# XMICRO_BP8.net
KiCad netlist of a schematic drawn in EAGLE
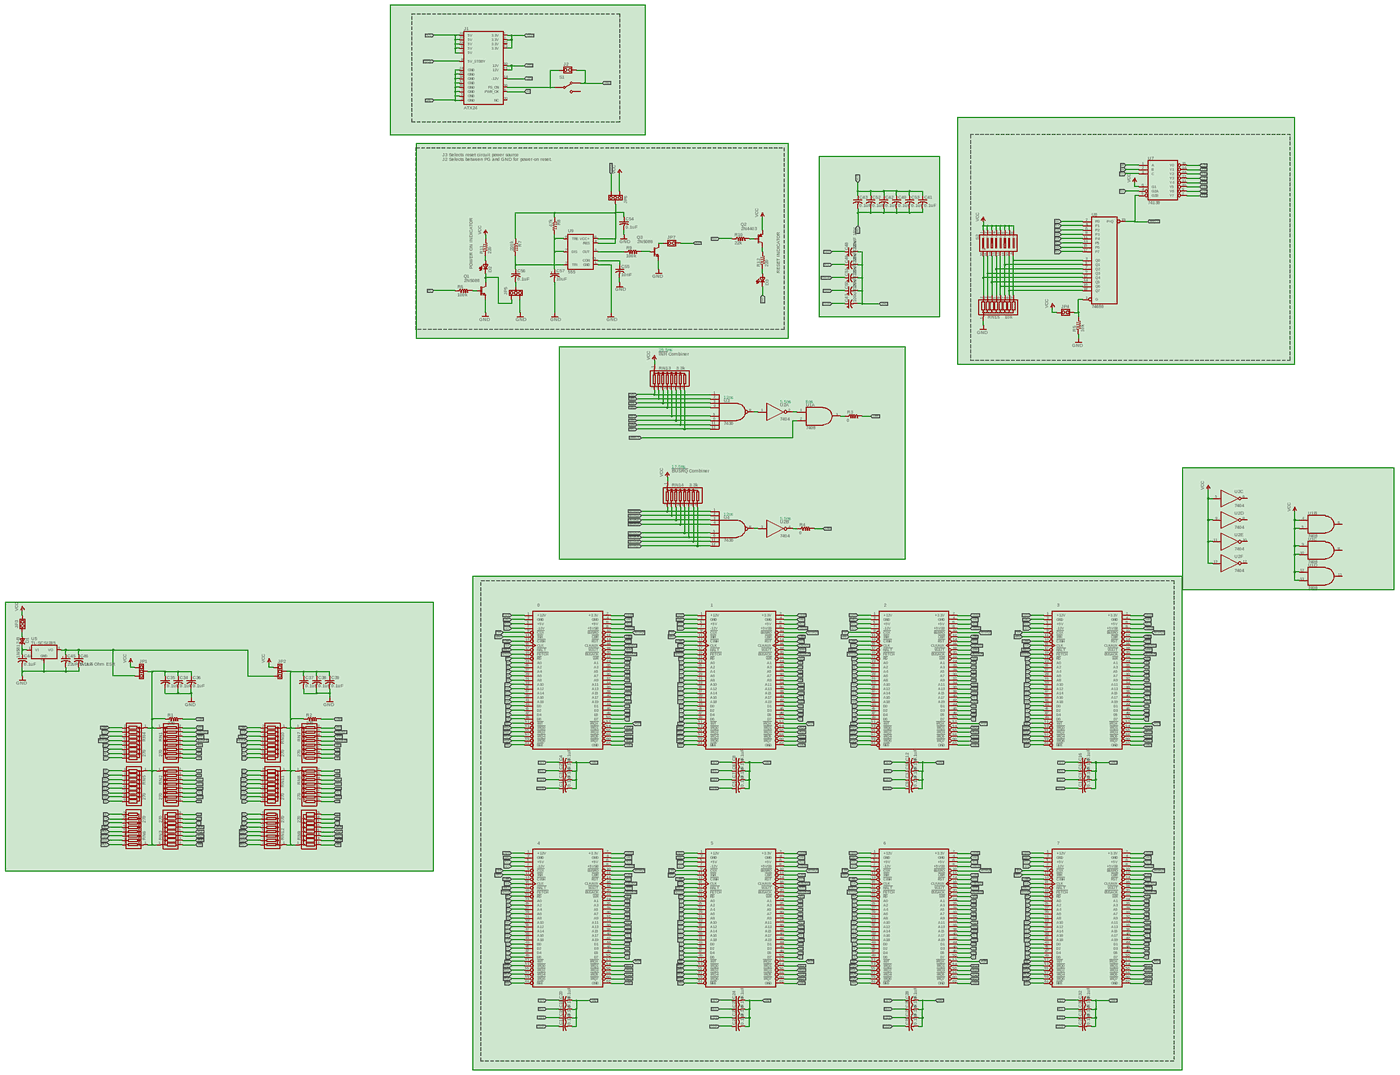
[diagram p0: schematic, sheet 1, overview]
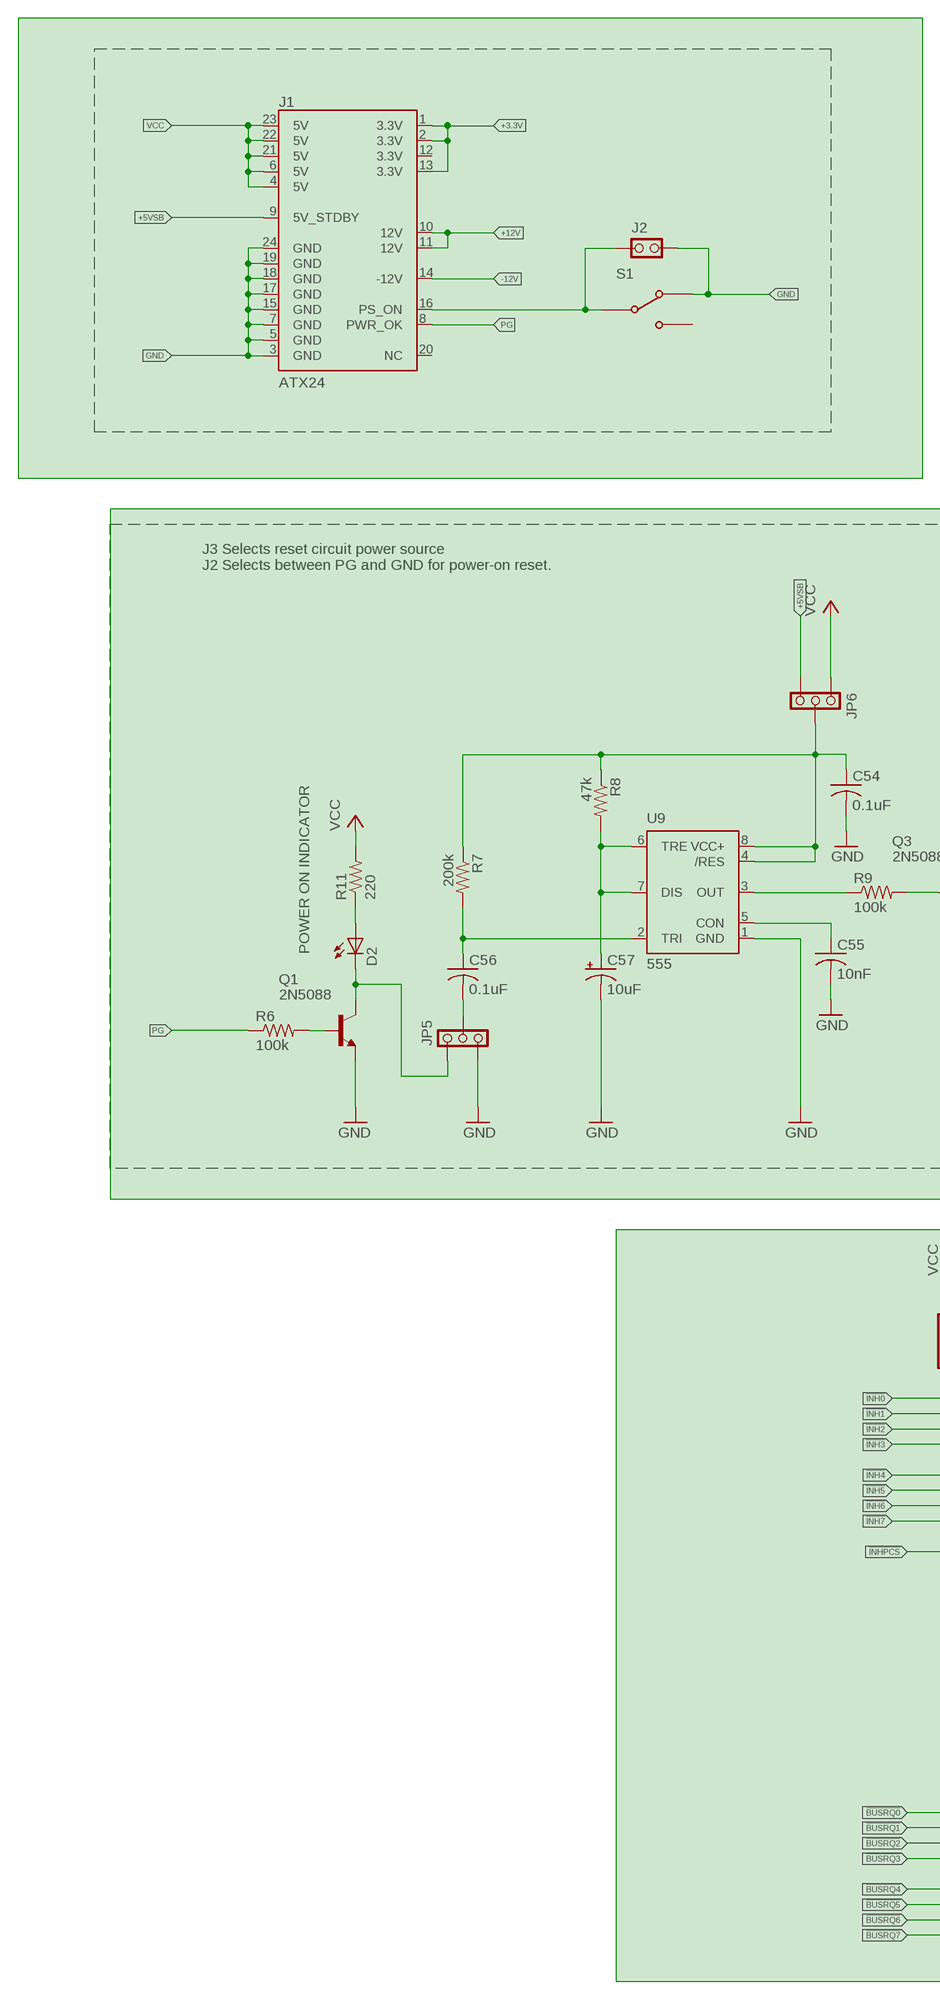
[diagram p1: schematic, sheet 1, part 1 of 4]
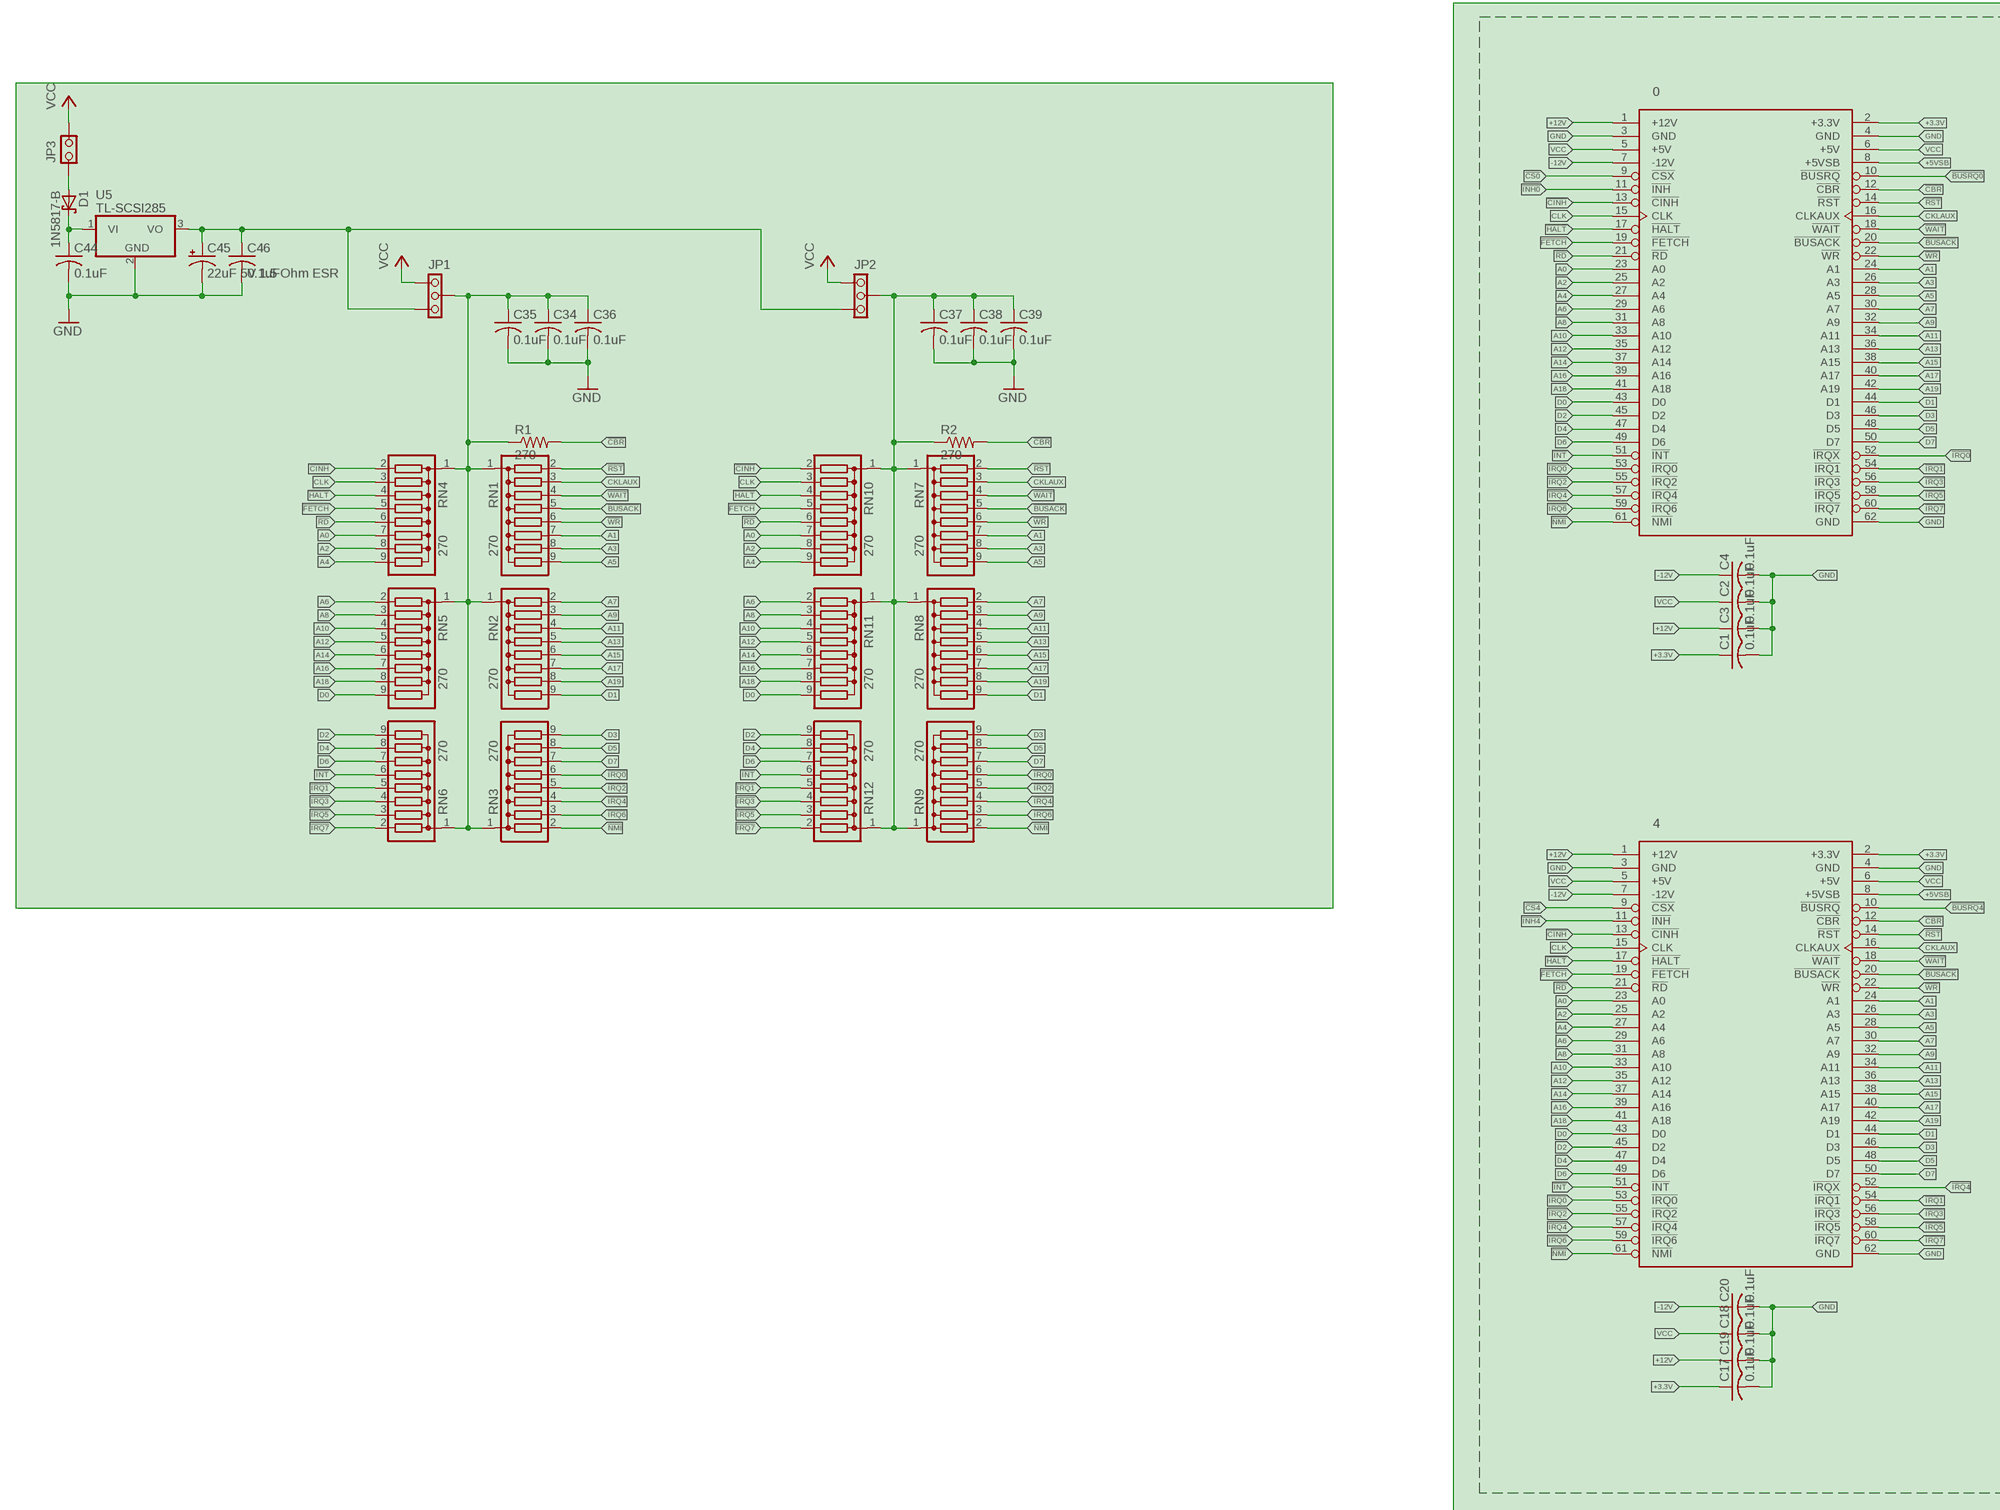
[diagram p2: schematic, sheet 1, part 2 of 4]
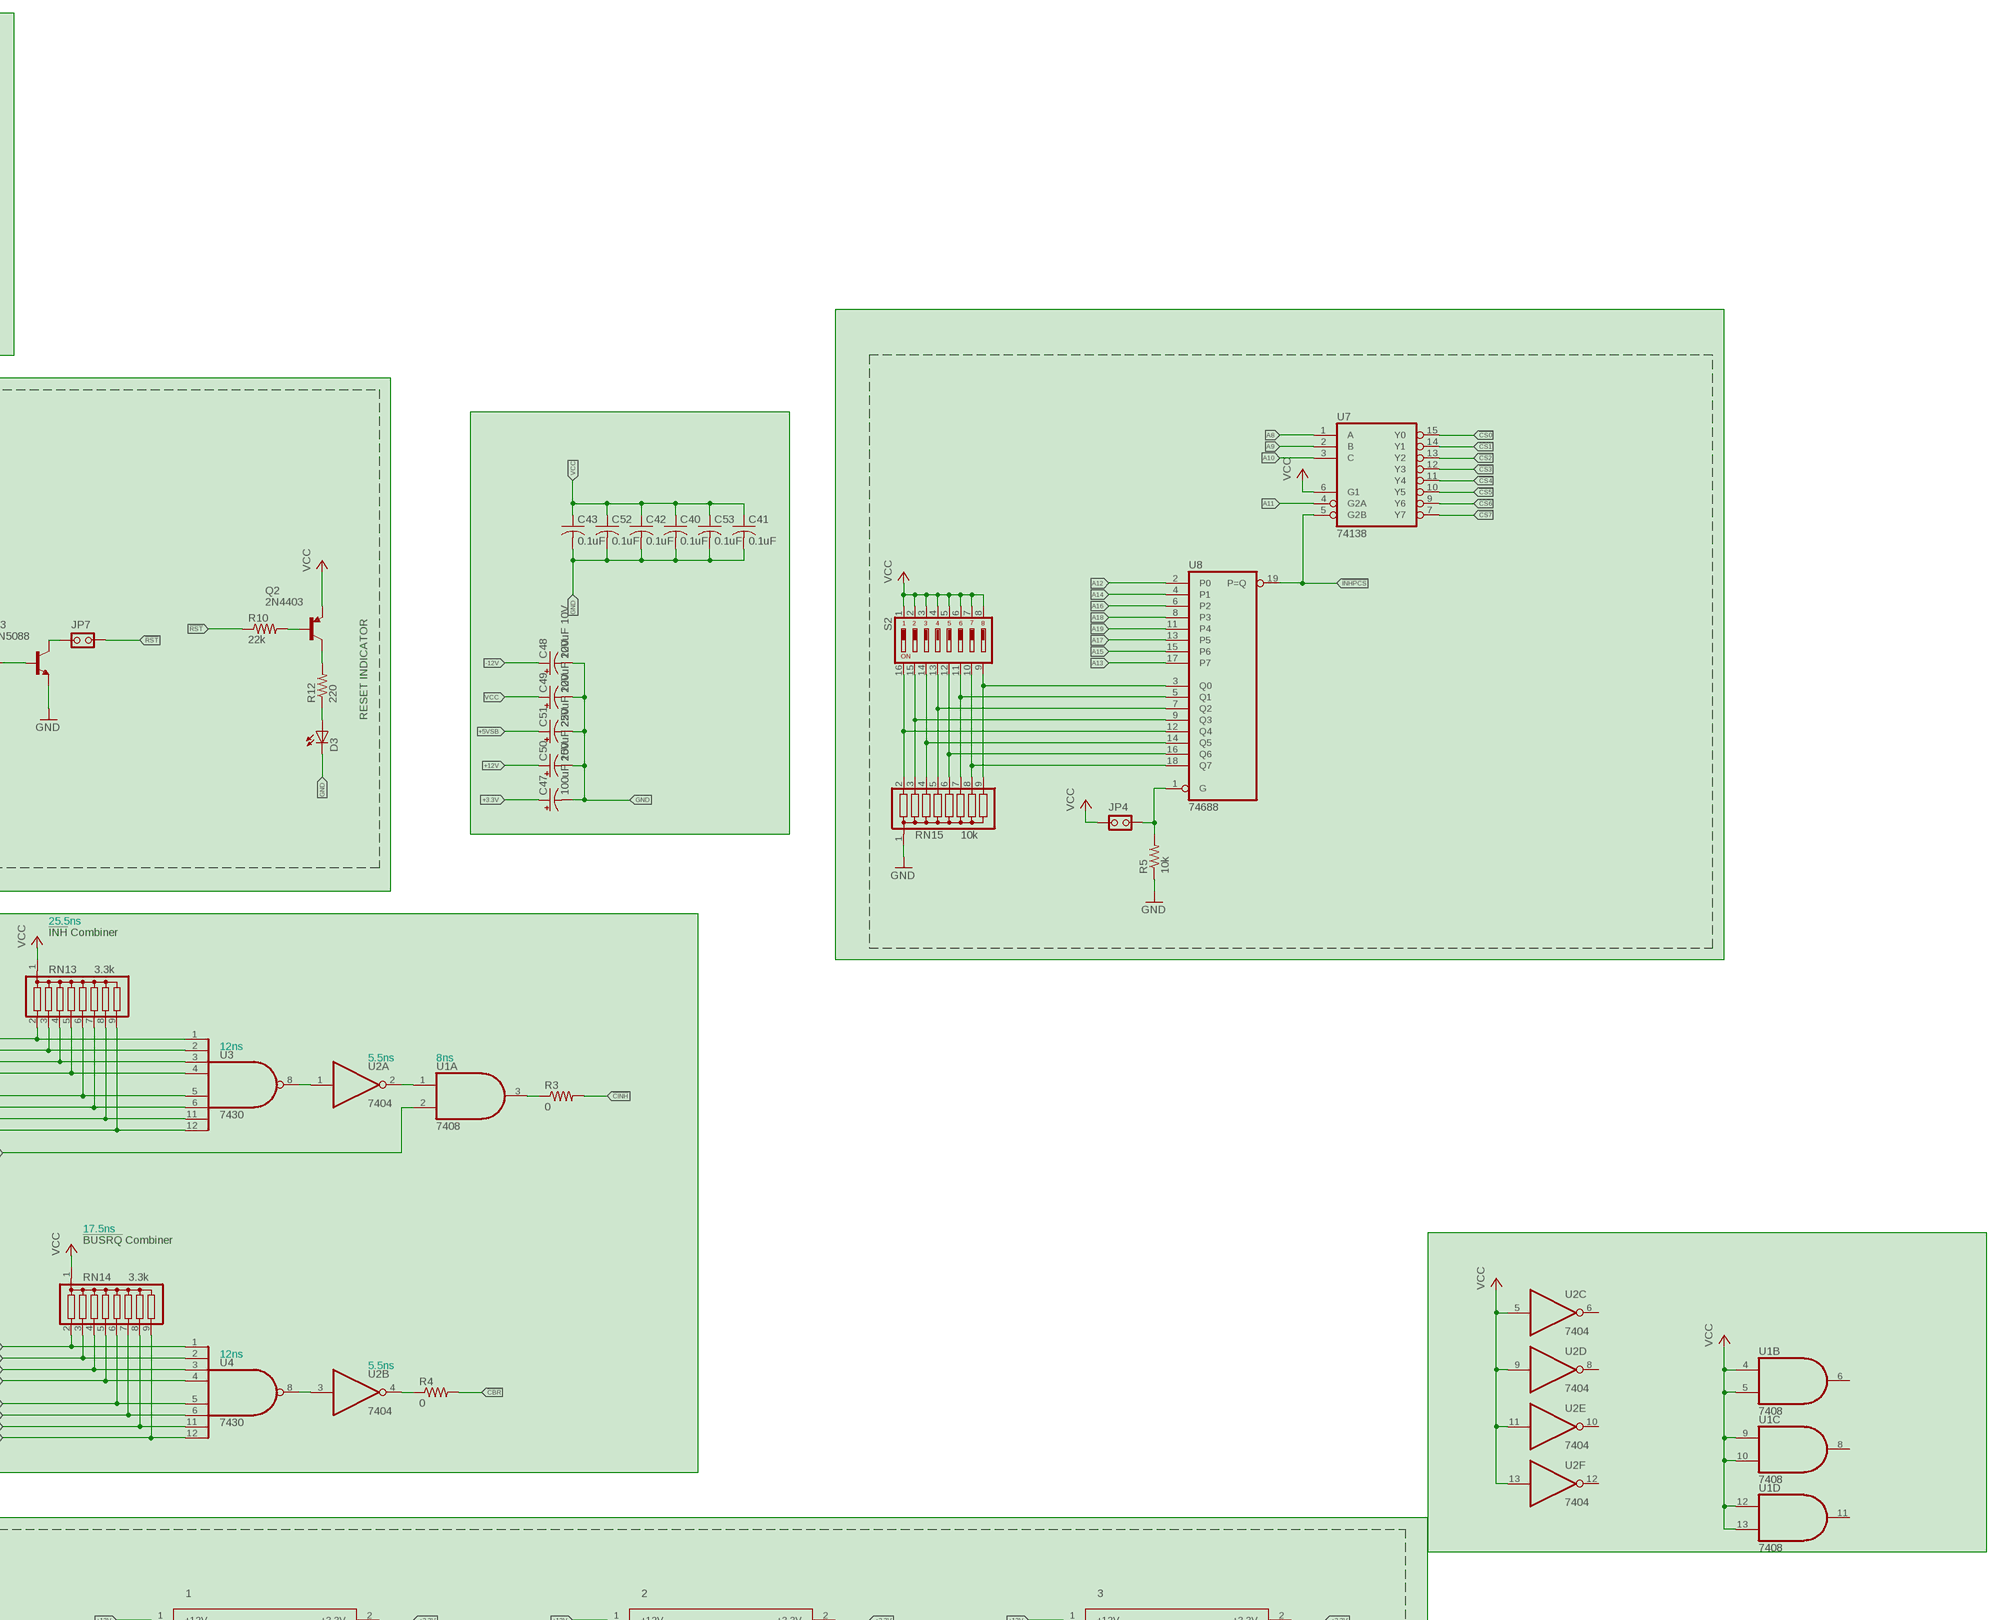
[diagram p3: schematic, sheet 1, part 3 of 4]
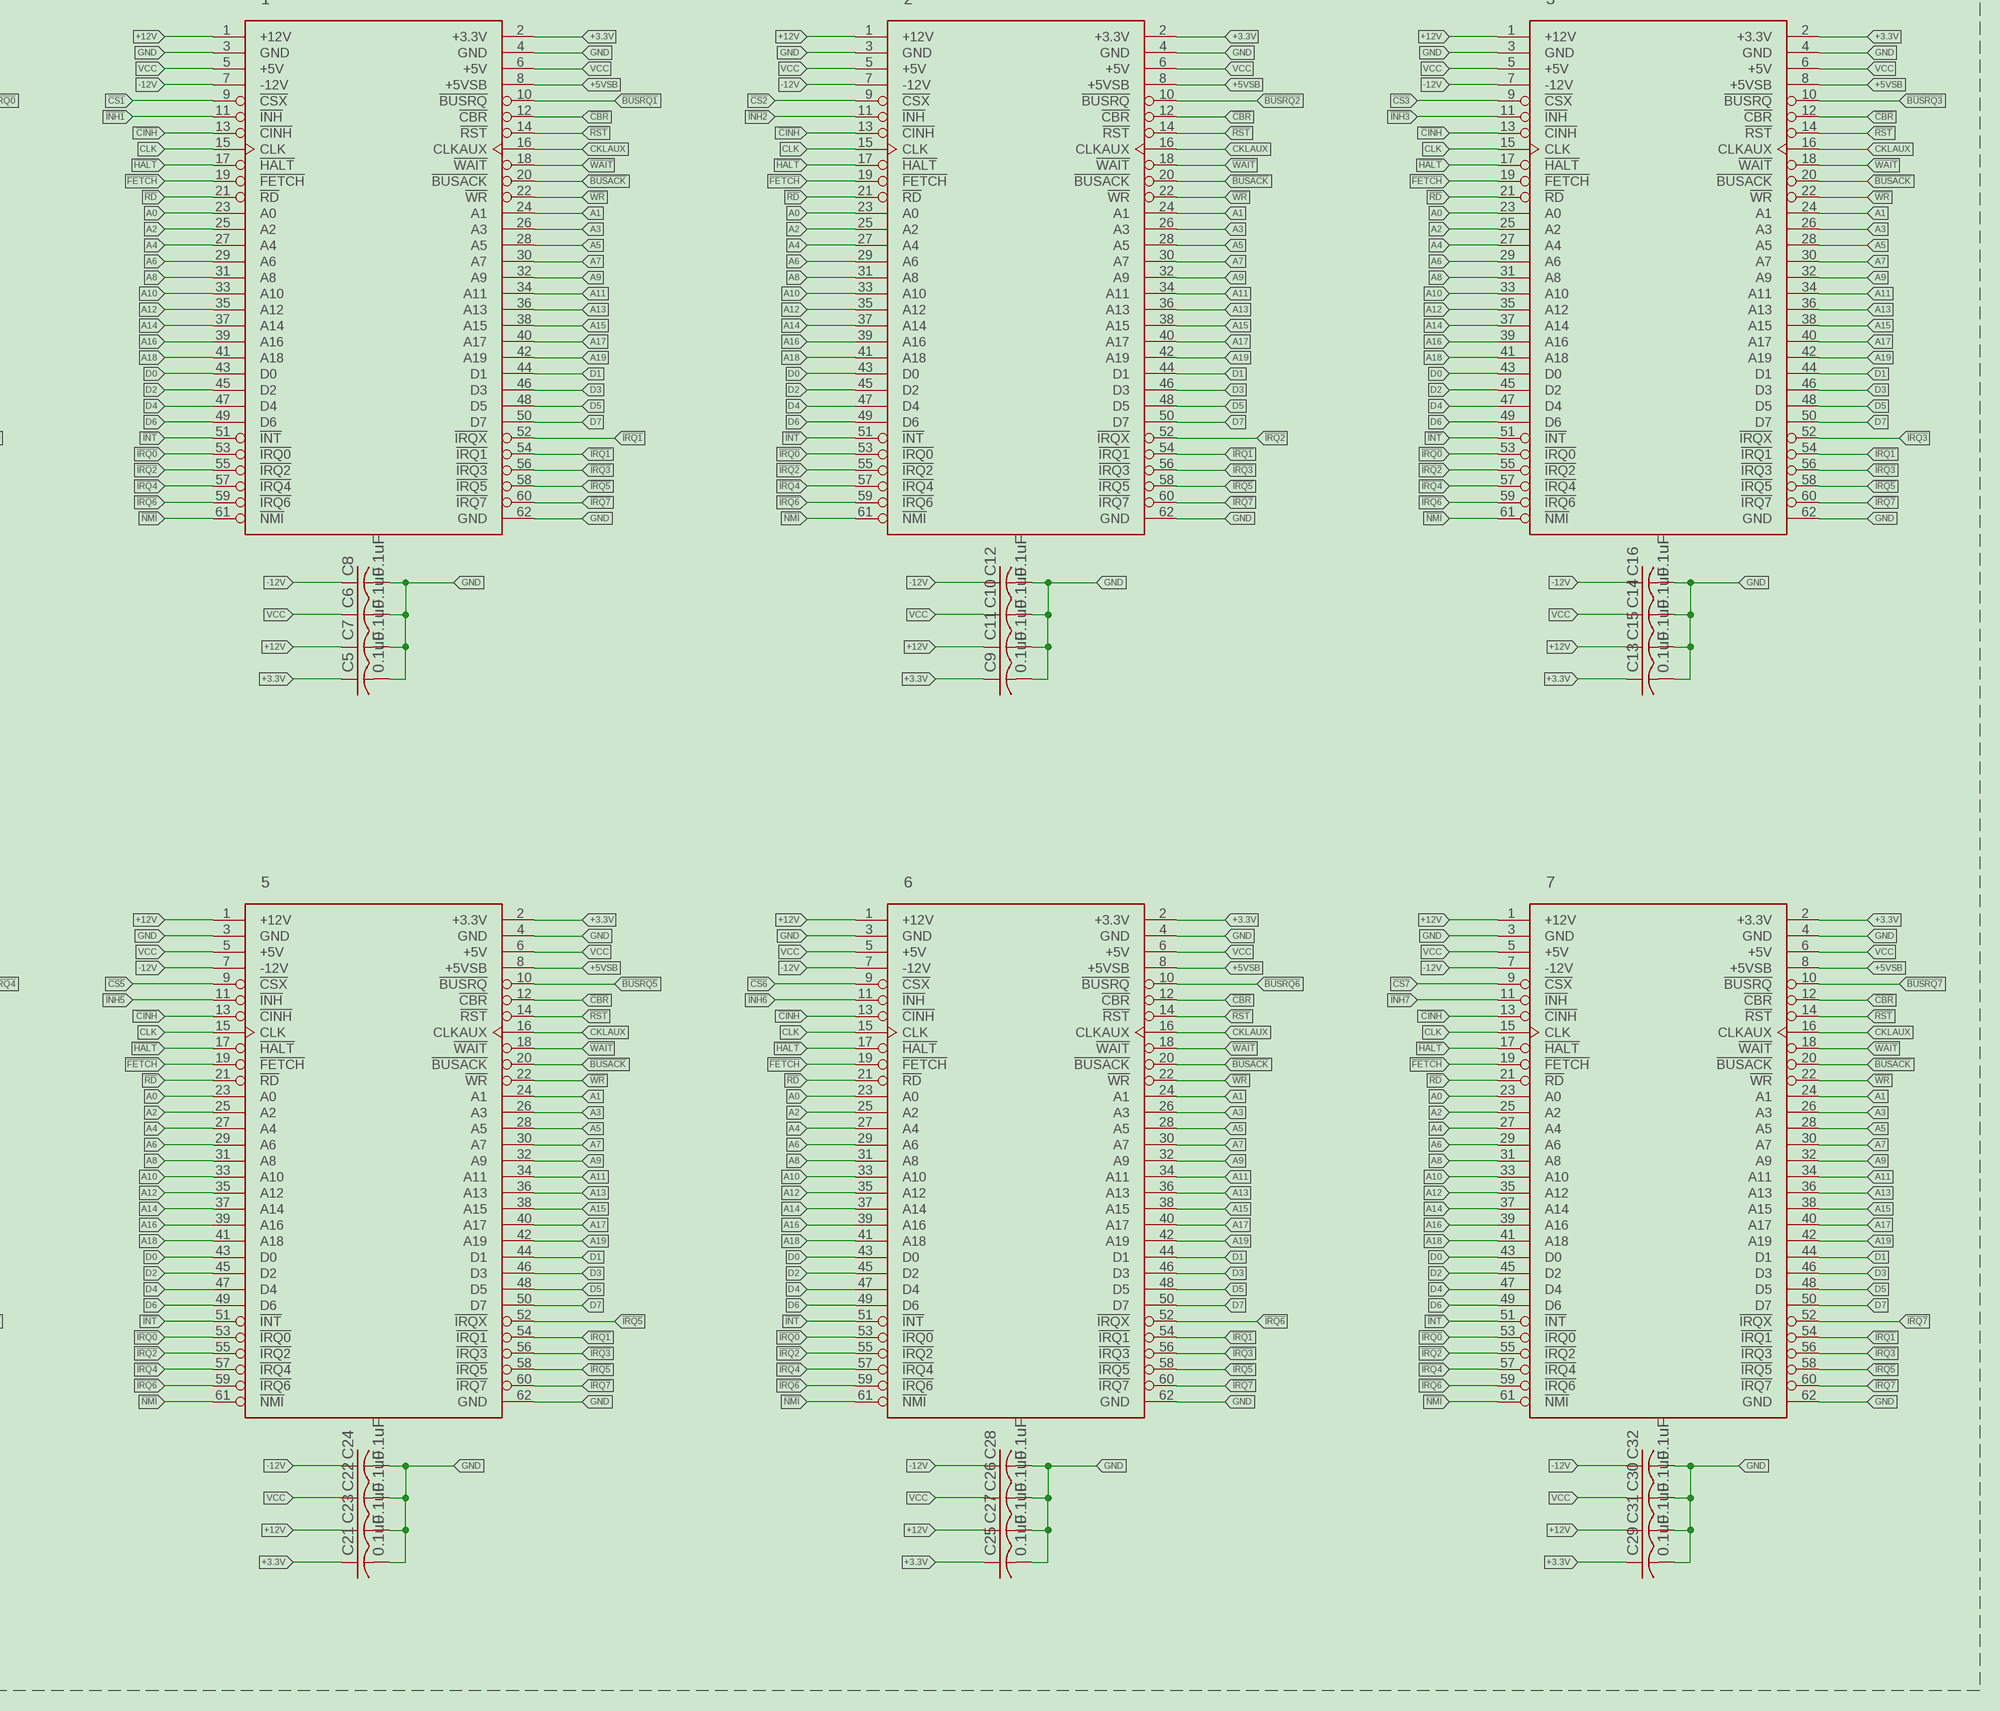
[diagram p4: schematic, sheet 1, part 4 of 4]

(export (version "E")
  (design (tool "Eeschema 10.0.6"))
  (components
    (comp (ref "0")
      (value "XMICRO-BUS-PHYSICAL-EDGE62F")
      (footprint "eagle-import:EDGE62F")
      (libsource (lib "eagle-import") (part "XMICRO-BUS-PHYSICAL-EDGE62F"))
    )
    (comp (ref "1")
      (value "XMICRO-BUS-PHYSICAL-EDGE62F")
      (footprint "eagle-import:EDGE62F")
      (libsource (lib "eagle-import") (part "XMICRO-BUS-PHYSICAL-EDGE62F"))
    )
    (comp (ref "2")
      (value "XMICRO-BUS-PHYSICAL-EDGE62F")
      (footprint "eagle-import:EDGE62F")
      (libsource (lib "eagle-import") (part "XMICRO-BUS-PHYSICAL-EDGE62F"))
    )
    (comp (ref "3")
      (value "XMICRO-BUS-PHYSICAL-EDGE62F")
      (footprint "eagle-import:EDGE62F")
      (libsource (lib "eagle-import") (part "XMICRO-BUS-PHYSICAL-EDGE62F"))
    )
    (comp (ref "4")
      (value "XMICRO-BUS-PHYSICAL-EDGE62F")
      (footprint "eagle-import:EDGE62F")
      (libsource (lib "eagle-import") (part "XMICRO-BUS-PHYSICAL-EDGE62F"))
    )
    (comp (ref "5")
      (value "XMICRO-BUS-PHYSICAL-EDGE62F")
      (footprint "eagle-import:EDGE62F")
      (libsource (lib "eagle-import") (part "XMICRO-BUS-PHYSICAL-EDGE62F"))
    )
    (comp (ref "6")
      (value "XMICRO-BUS-PHYSICAL-EDGE62F")
      (footprint "eagle-import:EDGE62F")
      (libsource (lib "eagle-import") (part "XMICRO-BUS-PHYSICAL-EDGE62F"))
    )
    (comp (ref "7")
      (value "XMICRO-BUS-PHYSICAL-EDGE62F")
      (footprint "eagle-import:EDGE62F")
      (libsource (lib "eagle-import") (part "XMICRO-BUS-PHYSICAL-EDGE62F"))
    )
    (comp (ref "C1")
      (value "0.1uF")
      (footprint "eagle-import:C025-024X044")
      (libsource (lib "eagle-import") (part "C-US025-024X044"))
    )
    (comp (ref "C2")
      (value "0.1uF")
      (footprint "eagle-import:C025-024X044")
      (libsource (lib "eagle-import") (part "C-US025-024X044"))
    )
    (comp (ref "C3")
      (value "0.1uF")
      (footprint "eagle-import:C025-024X044")
      (libsource (lib "eagle-import") (part "C-US025-024X044"))
    )
    (comp (ref "C4")
      (value "0.1uF")
      (footprint "eagle-import:C050-024X044")
      (libsource (lib "eagle-import") (part "C-US050-024X044"))
    )
    (comp (ref "C5")
      (value "0.1uF")
      (footprint "eagle-import:C025-024X044")
      (libsource (lib "eagle-import") (part "C-US025-024X044"))
    )
    (comp (ref "C6")
      (value "0.1uF")
      (footprint "eagle-import:C025-024X044")
      (libsource (lib "eagle-import") (part "C-US025-024X044"))
    )
    (comp (ref "C7")
      (value "0.1uF")
      (footprint "eagle-import:C025-024X044")
      (libsource (lib "eagle-import") (part "C-US025-024X044"))
    )
    (comp (ref "C8")
      (value "0.1uF")
      (footprint "eagle-import:C050-024X044")
      (libsource (lib "eagle-import") (part "C-US050-024X044"))
    )
    (comp (ref "C9")
      (value "0.1uF")
      (footprint "eagle-import:C025-024X044")
      (libsource (lib "eagle-import") (part "C-US025-024X044"))
    )
    (comp (ref "C10")
      (value "0.1uF")
      (footprint "eagle-import:C025-024X044")
      (libsource (lib "eagle-import") (part "C-US025-024X044"))
    )
    (comp (ref "C11")
      (value "0.1uF")
      (footprint "eagle-import:C025-024X044")
      (libsource (lib "eagle-import") (part "C-US025-024X044"))
    )
    (comp (ref "C12")
      (value "0.1uF")
      (footprint "eagle-import:C050-024X044")
      (libsource (lib "eagle-import") (part "C-US050-024X044"))
    )
    (comp (ref "C13")
      (value "0.1uF")
      (footprint "eagle-import:C025-024X044")
      (libsource (lib "eagle-import") (part "C-US025-024X044"))
    )
    (comp (ref "C14")
      (value "0.1uF")
      (footprint "eagle-import:C025-024X044")
      (libsource (lib "eagle-import") (part "C-US025-024X044"))
    )
    (comp (ref "C15")
      (value "0.1uF")
      (footprint "eagle-import:C025-024X044")
      (libsource (lib "eagle-import") (part "C-US025-024X044"))
    )
    (comp (ref "C16")
      (value "0.1uF")
      (footprint "eagle-import:C050-024X044")
      (libsource (lib "eagle-import") (part "C-US050-024X044"))
    )
    (comp (ref "C17")
      (value "0.1uF")
      (footprint "eagle-import:C025-024X044")
      (libsource (lib "eagle-import") (part "C-US025-024X044"))
    )
    (comp (ref "C18")
      (value "0.1uF")
      (footprint "eagle-import:C025-024X044")
      (libsource (lib "eagle-import") (part "C-US025-024X044"))
    )
    (comp (ref "C19")
      (value "0.1uF")
      (footprint "eagle-import:C025-024X044")
      (libsource (lib "eagle-import") (part "C-US025-024X044"))
    )
    (comp (ref "C20")
      (value "0.1uF")
      (footprint "eagle-import:C050-024X044")
      (libsource (lib "eagle-import") (part "C-US050-024X044"))
    )
    (comp (ref "C21")
      (value "0.1uF")
      (footprint "eagle-import:C025-024X044")
      (libsource (lib "eagle-import") (part "C-US025-024X044"))
    )
    (comp (ref "C22")
      (value "0.1uF")
      (footprint "eagle-import:C025-024X044")
      (libsource (lib "eagle-import") (part "C-US025-024X044"))
    )
    (comp (ref "C23")
      (value "0.1uF")
      (footprint "eagle-import:C025-024X044")
      (libsource (lib "eagle-import") (part "C-US025-024X044"))
    )
    (comp (ref "C24")
      (value "0.1uF")
      (footprint "eagle-import:C050-024X044")
      (libsource (lib "eagle-import") (part "C-US050-024X044"))
    )
    (comp (ref "C25")
      (value "0.1uF")
      (footprint "eagle-import:C025-024X044")
      (libsource (lib "eagle-import") (part "C-US025-024X044"))
    )
    (comp (ref "C26")
      (value "0.1uF")
      (footprint "eagle-import:C025-024X044")
      (libsource (lib "eagle-import") (part "C-US025-024X044"))
    )
    (comp (ref "C27")
      (value "0.1uF")
      (footprint "eagle-import:C025-024X044")
      (libsource (lib "eagle-import") (part "C-US025-024X044"))
    )
    (comp (ref "C28")
      (value "0.1uF")
      (footprint "eagle-import:C050-024X044")
      (libsource (lib "eagle-import") (part "C-US050-024X044"))
    )
    (comp (ref "C29")
      (value "0.1uF")
      (footprint "eagle-import:C025-024X044")
      (libsource (lib "eagle-import") (part "C-US025-024X044"))
    )
    (comp (ref "C30")
      (value "0.1uF")
      (footprint "eagle-import:C025-024X044")
      (libsource (lib "eagle-import") (part "C-US025-024X044"))
    )
    (comp (ref "C31")
      (value "0.1uF")
      (footprint "eagle-import:C025-024X044")
      (libsource (lib "eagle-import") (part "C-US025-024X044"))
    )
    (comp (ref "C32")
      (value "0.1uF")
      (footprint "eagle-import:C025-024X044")
      (libsource (lib "eagle-import") (part "C-US025-024X044"))
    )
    (comp (ref "C34")
      (value "0.1uF")
      (footprint "eagle-import:C025-024X044")
      (libsource (lib "eagle-import") (part "C-US025-024X044"))
    )
    (comp (ref "C35")
      (value "0.1uF")
      (footprint "eagle-import:C025-024X044")
      (libsource (lib "eagle-import") (part "C-US025-024X044"))
    )
    (comp (ref "C36")
      (value "0.1uF")
      (footprint "eagle-import:C025-024X044")
      (libsource (lib "eagle-import") (part "C-US025-024X044"))
    )
    (comp (ref "C37")
      (value "0.1uF")
      (footprint "eagle-import:C025-024X044")
      (libsource (lib "eagle-import") (part "C-US025-024X044"))
    )
    (comp (ref "C38")
      (value "0.1uF")
      (footprint "eagle-import:C025-024X044")
      (libsource (lib "eagle-import") (part "C-US025-024X044"))
    )
    (comp (ref "C39")
      (value "0.1uF")
      (footprint "eagle-import:C025-024X044")
      (libsource (lib "eagle-import") (part "C-US025-024X044"))
    )
    (comp (ref "C40")
      (value "0.1uF")
      (footprint "eagle-import:C025-024X044")
      (libsource (lib "eagle-import") (part "C-US025-024X044"))
    )
    (comp (ref "C41")
      (value "0.1uF")
      (footprint "eagle-import:C025-024X044")
      (libsource (lib "eagle-import") (part "C-US025-024X044"))
    )
    (comp (ref "C42")
      (value "0.1uF")
      (footprint "eagle-import:C025-024X044")
      (libsource (lib "eagle-import") (part "C-US025-024X044"))
    )
    (comp (ref "C43")
      (value "0.1uF")
      (footprint "eagle-import:C025-024X044")
      (libsource (lib "eagle-import") (part "C-US025-024X044"))
    )
    (comp (ref "C44")
      (value "0.1uF")
      (footprint "eagle-import:C025-024X044")
      (libsource (lib "eagle-import") (part "C-US025-024X044"))
    )
    (comp (ref "C45")
      (value "22uF 5V 1.5 Ohm ESR")
      (footprint "eagle-import:E2,5-7")
      (libsource (lib "eagle-import") (part "CPOL-USE2.5-7"))
    )
    (comp (ref "C46")
      (value "0.1uF")
      (footprint "eagle-import:C050-024X044")
      (libsource (lib "eagle-import") (part "C-US050-024X044"))
    )
    (comp (ref "C47")
      (value "100uF 25V")
      (footprint "eagle-import:C-10-5")
      (libsource (lib "eagle-import") (part "CPOL-US-10-5"))
    )
    (comp (ref "C48")
      (value "220uF 10V")
      (footprint "eagle-import:C-10-5")
      (libsource (lib "eagle-import") (part "CPOL-US-10-5"))
    )
    (comp (ref "C49")
      (value "220uF 10V")
      (footprint "eagle-import:C-10-5")
      (libsource (lib "eagle-import") (part "CPOL-US-10-5"))
    )
    (comp (ref "C50")
      (value "100uF 25V")
      (footprint "eagle-import:C-10-5")
      (libsource (lib "eagle-import") (part "CPOL-US-10-5"))
    )
    (comp (ref "C51")
      (value "220uF 10V")
      (footprint "eagle-import:C-10-5")
      (libsource (lib "eagle-import") (part "CPOL-US-10-5"))
    )
    (comp (ref "C52")
      (value "0.1uF")
      (footprint "eagle-import:C025-024X044")
      (libsource (lib "eagle-import") (part "C-US025-024X044"))
    )
    (comp (ref "C53")
      (value "0.1uF")
      (footprint "eagle-import:C025-024X044")
      (libsource (lib "eagle-import") (part "C-US025-024X044"))
    )
    (comp (ref "C54")
      (value "0.1uF")
      (footprint "eagle-import:C025-024X044")
      (libsource (lib "eagle-import") (part "C-US025-024X044"))
    )
    (comp (ref "C55")
      (value "10nF")
      (footprint "eagle-import:C025-024X044")
      (libsource (lib "eagle-import") (part "C-US025-024X044"))
    )
    (comp (ref "C56")
      (value "0.1uF")
      (footprint "eagle-import:C025-024X044")
      (libsource (lib "eagle-import") (part "C-US025-024X044"))
    )
    (comp (ref "C57")
      (value "10uF")
      (footprint "eagle-import:E2,5-7")
      (libsource (lib "eagle-import") (part "CPOL-USE2.5-7"))
    )
    (comp (ref "D1")
      (value "1N5817-B")
      (footprint "eagle-import:DO41-7.6")
      (libsource (lib "eagle-import") (part "1N5817-B"))
    )
    (comp (ref "D2")
      (value "LED5MM")
      (footprint "eagle-import:LED5MM")
      (libsource (lib "eagle-import") (part "LED5MM"))
    )
    (comp (ref "D3")
      (value "LED5MM")
      (footprint "eagle-import:LED5MM")
      (libsource (lib "eagle-import") (part "LED5MM"))
    )
    (comp (ref "J1")
      (value "ATX24")
      (footprint "eagle-import:ATX24")
      (libsource (lib "eagle-import") (part "ATX24"))
    )
    (comp (ref "J2")
      (value "PINHD-1X2THRU")
      (footprint "eagle-import:1X02")
      (libsource (lib "eagle-import") (part "PINHD-1X2THRU"))
    )
    (comp (ref "JP1")
      (value "PINHD1X3THRU")
      (footprint "eagle-import:1X03")
      (libsource (lib "eagle-import") (part "PINHD1X3THRU"))
    )
    (comp (ref "JP2")
      (value "PINHD1X3THRU")
      (footprint "eagle-import:1X03")
      (libsource (lib "eagle-import") (part "PINHD1X3THRU"))
    )
    (comp (ref "JP3")
      (value "PINHD-1X2THRU")
      (footprint "eagle-import:1X02")
      (libsource (lib "eagle-import") (part "PINHD-1X2THRU"))
    )
    (comp (ref "JP4")
      (value "PINHD-1X2THRU")
      (footprint "eagle-import:1X02")
      (libsource (lib "eagle-import") (part "PINHD-1X2THRU"))
    )
    (comp (ref "JP5")
      (value "PINHD1X3THRU")
      (footprint "eagle-import:1X03")
      (libsource (lib "eagle-import") (part "PINHD1X3THRU"))
    )
    (comp (ref "JP6")
      (value "PINHD1X3THRU")
      (footprint "eagle-import:1X03")
      (libsource (lib "eagle-import") (part "PINHD1X3THRU"))
    )
    (comp (ref "JP7")
      (value "PINHD-1X2THRU")
      (footprint "eagle-import:1X02")
      (libsource (lib "eagle-import") (part "PINHD-1X2THRU"))
    )
    (comp (ref "Q1")
      (value "2N5088")
      (footprint "eagle-import:TO92")
      (libsource (lib "eagle-import") (part "TRANSISTOR-NPN-2N5088"))
    )
    (comp (ref "Q2")
      (value "2N4403")
      (footprint "eagle-import:TO92")
      (libsource (lib "eagle-import") (part "TRANSISTOR-PNP-2N4403"))
    )
    (comp (ref "Q3")
      (value "2N5088")
      (footprint "eagle-import:TO92")
      (libsource (lib "eagle-import") (part "TRANSISTOR-NPN-2N5088"))
    )
    (comp (ref "R1")
      (value "270")
      (footprint "eagle-import:0207_10")
      (libsource (lib "eagle-import") (part "R-US_0207/10"))
    )
    (comp (ref "R2")
      (value "270")
      (footprint "eagle-import:0207_10")
      (libsource (lib "eagle-import") (part "R-US_0207/10"))
    )
    (comp (ref "R3")
      (value "0")
      (footprint "eagle-import:0207_10")
      (libsource (lib "eagle-import") (part "R-US_0207/10"))
    )
    (comp (ref "R4")
      (value "0")
      (footprint "eagle-import:0207_10")
      (libsource (lib "eagle-import") (part "R-US_0207/10"))
    )
    (comp (ref "R5")
      (value "10k")
      (footprint "eagle-import:0207_10")
      (libsource (lib "eagle-import") (part "R-US_0207/10"))
    )
    (comp (ref "R6")
      (value "100k")
      (footprint "eagle-import:0207_10")
      (libsource (lib "eagle-import") (part "R-US_0207/10"))
    )
    (comp (ref "R7")
      (value "200k")
      (footprint "eagle-import:0207_10")
      (libsource (lib "eagle-import") (part "R-US_0207/10"))
    )
    (comp (ref "R8")
      (value "47k")
      (footprint "eagle-import:0207_10")
      (libsource (lib "eagle-import") (part "R-US_0207/10"))
    )
    (comp (ref "R9")
      (value "100k")
      (footprint "eagle-import:0207_10")
      (libsource (lib "eagle-import") (part "R-US_0207/10"))
    )
    (comp (ref "R10")
      (value "22k")
      (footprint "eagle-import:0207_10")
      (libsource (lib "eagle-import") (part "R-US_0207/10"))
    )
    (comp (ref "R11")
      (value "220")
      (footprint "eagle-import:0207_10")
      (libsource (lib "eagle-import") (part "R-US_0207/10"))
    )
    (comp (ref "R12")
      (value "220")
      (footprint "eagle-import:0207_10")
      (libsource (lib "eagle-import") (part "R-US_0207/10"))
    )
    (comp (ref "RN1")
      (value "270")
      (footprint "eagle-import:SIL9")
      (fields (field (name "OC_FARNELL") "unknown") (field (name "OC_NEWARK") "unknown"))
      (libsource (lib "eagle-import") (part "G08R"))
    )
    (comp (ref "RN2")
      (value "270")
      (footprint "eagle-import:SIL9")
      (fields (field (name "OC_FARNELL") "unknown") (field (name "OC_NEWARK") "unknown"))
      (libsource (lib "eagle-import") (part "G08R"))
    )
    (comp (ref "RN3")
      (value "270")
      (footprint "eagle-import:SIL9")
      (fields (field (name "OC_FARNELL") "unknown") (field (name "OC_NEWARK") "unknown"))
      (libsource (lib "eagle-import") (part "G08R"))
    )
    (comp (ref "RN4")
      (value "270")
      (footprint "eagle-import:SIL9")
      (fields (field (name "OC_FARNELL") "unknown") (field (name "OC_NEWARK") "unknown"))
      (libsource (lib "eagle-import") (part "G08R"))
    )
    (comp (ref "RN5")
      (value "270")
      (footprint "eagle-import:SIL9")
      (fields (field (name "OC_FARNELL") "unknown") (field (name "OC_NEWARK") "unknown"))
      (libsource (lib "eagle-import") (part "G08R"))
    )
    (comp (ref "RN6")
      (value "270")
      (footprint "eagle-import:SIL9")
      (fields (field (name "OC_FARNELL") "unknown") (field (name "OC_NEWARK") "unknown"))
      (libsource (lib "eagle-import") (part "G08R"))
    )
    (comp (ref "RN7")
      (value "270")
      (footprint "eagle-import:SIL9")
      (fields (field (name "OC_FARNELL") "unknown") (field (name "OC_NEWARK") "unknown"))
      (libsource (lib "eagle-import") (part "G08R"))
    )
    (comp (ref "RN8")
      (value "270")
      (footprint "eagle-import:SIL9")
      (fields (field (name "OC_FARNELL") "unknown") (field (name "OC_NEWARK") "unknown"))
      (libsource (lib "eagle-import") (part "G08R"))
    )
    (comp (ref "RN9")
      (value "270")
      (footprint "eagle-import:SIL9")
      (fields (field (name "OC_FARNELL") "unknown") (field (name "OC_NEWARK") "unknown"))
      (libsource (lib "eagle-import") (part "G08R"))
    )
    (comp (ref "RN10")
      (value "270")
      (footprint "eagle-import:SIL9")
      (fields (field (name "OC_FARNELL") "unknown") (field (name "OC_NEWARK") "unknown"))
      (libsource (lib "eagle-import") (part "G08R"))
    )
    (comp (ref "RN11")
      (value "270")
      (footprint "eagle-import:SIL9")
      (fields (field (name "OC_FARNELL") "unknown") (field (name "OC_NEWARK") "unknown"))
      (libsource (lib "eagle-import") (part "G08R"))
    )
    (comp (ref "RN12")
      (value "270")
      (footprint "eagle-import:SIL9")
      (fields (field (name "OC_FARNELL") "unknown") (field (name "OC_NEWARK") "unknown"))
      (libsource (lib "eagle-import") (part "G08R"))
    )
    (comp (ref "RN13")
      (value "3.3k")
      (footprint "eagle-import:SIL9")
      (fields (field (name "OC_FARNELL") "unknown") (field (name "OC_NEWARK") "unknown"))
      (libsource (lib "eagle-import") (part "G08R"))
    )
    (comp (ref "RN14")
      (value "3.3k")
      (footprint "eagle-import:SIL9")
      (fields (field (name "OC_FARNELL") "unknown") (field (name "OC_NEWARK") "unknown"))
      (libsource (lib "eagle-import") (part "G08R"))
    )
    (comp (ref "RN15")
      (value "10k")
      (footprint "eagle-import:SIL9")
      (fields (field (name "OC_FARNELL") "unknown") (field (name "OC_NEWARK") "unknown"))
      (libsource (lib "eagle-import") (part "G08R"))
    )
    (comp (ref "S1")
      (value "SPDTT411013")
      (footprint "eagle-import:T411013")
      (libsource (lib "eagle-import") (part "SPDTT411013"))
    )
    (comp (ref "S2")
      (value "SW-DIP08")
      (footprint "eagle-import:SW-DIP8")
      (libsource (lib "eagle-import") (part "SW-DIP08"))
    )
    (comp (ref "U1")
      (value "7408")
      (footprint "eagle-import:DIL14")
      (libsource (lib "eagle-import") (part "7408NLS"))
    )
    (comp (ref "U2")
      (value "7404")
      (footprint "eagle-import:DIL14")
      (libsource (lib "eagle-import") (part "7404NLS"))
    )
    (comp (ref "U3")
      (value "7430")
      (footprint "eagle-import:DIL14")
      (libsource (lib "eagle-import") (part "7430NLS"))
    )
    (comp (ref "U4")
      (value "7430")
      (footprint "eagle-import:DIL14")
      (libsource (lib "eagle-import") (part "7430NLS"))
    )
    (comp (ref "U5")
      (value "TL-SCSI285")
      (footprint "eagle-import:TO220H")
      (libsource (lib "eagle-import") (part "TL-SCSI285-TO220H"))
    )
    (comp (ref "U7")
      (value "74138")
      (footprint "eagle-import:DIL16")
      (libsource (lib "eagle-import") (part "74138NLS"))
    )
    (comp (ref "U8")
      (value "74688")
      (footprint "eagle-import:DIL20")
      (libsource (lib "eagle-import") (part "74688NLS"))
    )
    (comp (ref "U9")
      (value "555")
      (footprint "eagle-import:DIL-08")
      (fields (field (name "MF") "Arrow Electronics") (field (name "MPN") "NE555N"))
      (libsource (lib "eagle-import") (part "NE555"))
    )
  )
  (nets
    (net (code "1") (name "+3.3V") (class "Default")
      (node (ref "0") (pin "2") (pinfunction "+3.3V_2") (pintype "bidirectional"))
      (node (ref "1") (pin "2") (pinfunction "+3.3V_2") (pintype "bidirectional"))
      (node (ref "2") (pin "2") (pinfunction "+3.3V_2") (pintype "bidirectional"))
      (node (ref "3") (pin "2") (pinfunction "+3.3V_2") (pintype "bidirectional"))
      (node (ref "4") (pin "2") (pinfunction "+3.3V_2") (pintype "bidirectional"))
      (node (ref "5") (pin "2") (pinfunction "+3.3V_2") (pintype "bidirectional"))
      (node (ref "6") (pin "2") (pinfunction "+3.3V_2") (pintype "bidirectional"))
      (node (ref "7") (pin "2") (pinfunction "+3.3V_2") (pintype "bidirectional"))
      (node (ref "C1") (pin "1") (pinfunction "1_1") (pintype "passive"))
      (node (ref "C13") (pin "1") (pinfunction "1_1") (pintype "passive"))
      (node (ref "C17") (pin "1") (pinfunction "1_1") (pintype "passive"))
      (node (ref "C21") (pin "1") (pinfunction "1_1") (pintype "passive"))
      (node (ref "C25") (pin "1") (pinfunction "1_1") (pintype "passive"))
      (node (ref "C29") (pin "1") (pinfunction "1_1") (pintype "passive"))
      (node (ref "C47") (pin "+") (pinfunction "+_+") (pintype "passive"))
      (node (ref "C5") (pin "1") (pinfunction "1_1") (pintype "passive"))
      (node (ref "C9") (pin "1") (pinfunction "1_1") (pintype "passive"))
      (node (ref "J1") (pin "1") (pinfunction "3.3V_1") (pintype "bidirectional"))
      (node (ref "J1") (pin "13") (pinfunction "3.3V_13") (pintype "bidirectional"))
      (node (ref "J1") (pin "2") (pinfunction "3.3V_2") (pintype "bidirectional"))
    )
    (net (code "2") (name "+5VSB") (class "Default")
      (node (ref "0") (pin "8") (pinfunction "+5VSB_8") (pintype "bidirectional"))
      (node (ref "1") (pin "8") (pinfunction "+5VSB_8") (pintype "bidirectional"))
      (node (ref "2") (pin "8") (pinfunction "+5VSB_8") (pintype "bidirectional"))
      (node (ref "3") (pin "8") (pinfunction "+5VSB_8") (pintype "bidirectional"))
      (node (ref "4") (pin "8") (pinfunction "+5VSB_8") (pintype "bidirectional"))
      (node (ref "5") (pin "8") (pinfunction "+5VSB_8") (pintype "bidirectional"))
      (node (ref "6") (pin "8") (pinfunction "+5VSB_8") (pintype "bidirectional"))
      (node (ref "7") (pin "8") (pinfunction "+5VSB_8") (pintype "bidirectional"))
      (node (ref "C51") (pin "+") (pinfunction "+_+") (pintype "passive"))
      (node (ref "J1") (pin "9") (pinfunction "5V_STDBY_9") (pintype "bidirectional"))
      (node (ref "JP6") (pin "3") (pinfunction "3_3") (pintype "passive"))
    )
    (net (code "3") (name "+12V") (class "Default")
      (node (ref "0") (pin "1") (pinfunction "+12V_1") (pintype "bidirectional"))
      (node (ref "1") (pin "1") (pinfunction "+12V_1") (pintype "bidirectional"))
      (node (ref "2") (pin "1") (pinfunction "+12V_1") (pintype "bidirectional"))
      (node (ref "3") (pin "1") (pinfunction "+12V_1") (pintype "bidirectional"))
      (node (ref "4") (pin "1") (pinfunction "+12V_1") (pintype "bidirectional"))
      (node (ref "5") (pin "1") (pinfunction "+12V_1") (pintype "bidirectional"))
      (node (ref "6") (pin "1") (pinfunction "+12V_1") (pintype "bidirectional"))
      (node (ref "7") (pin "1") (pinfunction "+12V_1") (pintype "bidirectional"))
      (node (ref "C11") (pin "1") (pinfunction "1_1") (pintype "passive"))
      (node (ref "C15") (pin "1") (pinfunction "1_1") (pintype "passive"))
      (node (ref "C19") (pin "1") (pinfunction "1_1") (pintype "passive"))
      (node (ref "C23") (pin "1") (pinfunction "1_1") (pintype "passive"))
      (node (ref "C27") (pin "1") (pinfunction "1_1") (pintype "passive"))
      (node (ref "C3") (pin "1") (pinfunction "1_1") (pintype "passive"))
      (node (ref "C31") (pin "1") (pinfunction "1_1") (pintype "passive"))
      (node (ref "C50") (pin "+") (pinfunction "+_+") (pintype "passive"))
      (node (ref "C7") (pin "1") (pinfunction "1_1") (pintype "passive"))
      (node (ref "J1") (pin "10") (pinfunction "12V_10") (pintype "bidirectional"))
      (node (ref "J1") (pin "11") (pinfunction "12V_11") (pintype "bidirectional"))
    )
    (net (code "4") (name "-12V") (class "Default")
      (node (ref "0") (pin "7") (pinfunction "-12V_7") (pintype "bidirectional"))
      (node (ref "1") (pin "7") (pinfunction "-12V_7") (pintype "bidirectional"))
      (node (ref "2") (pin "7") (pinfunction "-12V_7") (pintype "bidirectional"))
      (node (ref "3") (pin "7") (pinfunction "-12V_7") (pintype "bidirectional"))
      (node (ref "4") (pin "7") (pinfunction "-12V_7") (pintype "bidirectional"))
      (node (ref "5") (pin "7") (pinfunction "-12V_7") (pintype "bidirectional"))
      (node (ref "6") (pin "7") (pinfunction "-12V_7") (pintype "bidirectional"))
      (node (ref "7") (pin "7") (pinfunction "-12V_7") (pintype "bidirectional"))
      (node (ref "C12") (pin "1") (pinfunction "1_1") (pintype "passive"))
      (node (ref "C16") (pin "1") (pinfunction "1_1") (pintype "passive"))
      (node (ref "C20") (pin "1") (pinfunction "1_1") (pintype "passive"))
      (node (ref "C24") (pin "1") (pinfunction "1_1") (pintype "passive"))
      (node (ref "C28") (pin "1") (pinfunction "1_1") (pintype "passive"))
      (node (ref "C32") (pin "1") (pinfunction "1_1") (pintype "passive"))
      (node (ref "C4") (pin "1") (pinfunction "1_1") (pintype "passive"))
      (node (ref "C48") (pin "+") (pinfunction "+_+") (pintype "passive"))
      (node (ref "C8") (pin "1") (pinfunction "1_1") (pintype "passive"))
      (node (ref "J1") (pin "14") (pinfunction "-12V_14") (pintype "bidirectional"))
    )
    (net (code "5") (name "/~{BUSACK}") (class "Default")
      (node (ref "0") (pin "20") (pinfunction "~{BUSACK}_20") (pintype "bidirectional"))
      (node (ref "1") (pin "20") (pinfunction "~{BUSACK}_20") (pintype "bidirectional"))
      (node (ref "2") (pin "20") (pinfunction "~{BUSACK}_20") (pintype "bidirectional"))
      (node (ref "3") (pin "20") (pinfunction "~{BUSACK}_20") (pintype "bidirectional"))
      (node (ref "4") (pin "20") (pinfunction "~{BUSACK}_20") (pintype "bidirectional"))
      (node (ref "5") (pin "20") (pinfunction "~{BUSACK}_20") (pintype "bidirectional"))
      (node (ref "6") (pin "20") (pinfunction "~{BUSACK}_20") (pintype "bidirectional"))
      (node (ref "7") (pin "20") (pinfunction "~{BUSACK}_20") (pintype "bidirectional"))
      (node (ref "RN1") (pin "5") (pinfunction "5_5") (pintype "passive"))
      (node (ref "RN7") (pin "5") (pinfunction "5_5") (pintype "passive"))
    )
    (net (code "6") (name "/~{BUSRQ0}") (class "Default")
      (node (ref "0") (pin "10") (pinfunction "~{BUSRQ}_10") (pintype "bidirectional"))
      (node (ref "RN14") (pin "2") (pinfunction "2_2") (pintype "passive"))
      (node (ref "U4") (pin "1") (pinfunction "I0_1") (pintype "input"))
    )
    (net (code "7") (name "/~{BUSRQ1}") (class "Default")
      (node (ref "1") (pin "10") (pinfunction "~{BUSRQ}_10") (pintype "bidirectional"))
      (node (ref "RN14") (pin "3") (pinfunction "3_3") (pintype "passive"))
      (node (ref "U4") (pin "2") (pinfunction "I1_2") (pintype "input"))
    )
    (net (code "8") (name "/~{BUSRQ2}") (class "Default")
      (node (ref "2") (pin "10") (pinfunction "~{BUSRQ}_10") (pintype "bidirectional"))
      (node (ref "RN14") (pin "4") (pinfunction "4_4") (pintype "passive"))
      (node (ref "U4") (pin "3") (pinfunction "I2_3") (pintype "input"))
    )
    (net (code "9") (name "/~{BUSRQ3}") (class "Default")
      (node (ref "3") (pin "10") (pinfunction "~{BUSRQ}_10") (pintype "bidirectional"))
      (node (ref "RN14") (pin "5") (pinfunction "5_5") (pintype "passive"))
      (node (ref "U4") (pin "4") (pinfunction "I3_4") (pintype "input"))
    )
    (net (code "10") (name "/~{BUSRQ4}") (class "Default")
      (node (ref "4") (pin "10") (pinfunction "~{BUSRQ}_10") (pintype "bidirectional"))
      (node (ref "RN14") (pin "6") (pinfunction "6_6") (pintype "passive"))
      (node (ref "U4") (pin "5") (pinfunction "I4_5") (pintype "input"))
    )
    (net (code "11") (name "/~{BUSRQ5}") (class "Default")
      (node (ref "5") (pin "10") (pinfunction "~{BUSRQ}_10") (pintype "bidirectional"))
      (node (ref "RN14") (pin "7") (pinfunction "7_7") (pintype "passive"))
      (node (ref "U4") (pin "6") (pinfunction "I5_6") (pintype "input"))
    )
    (net (code "12") (name "/~{BUSRQ6}") (class "Default")
      (node (ref "6") (pin "10") (pinfunction "~{BUSRQ}_10") (pintype "bidirectional"))
      (node (ref "RN14") (pin "8") (pinfunction "8_8") (pintype "passive"))
      (node (ref "U4") (pin "11") (pinfunction "I6_11") (pintype "input"))
    )
    (net (code "13") (name "/~{BUSRQ7}") (class "Default")
      (node (ref "7") (pin "10") (pinfunction "~{BUSRQ}_10") (pintype "bidirectional"))
      (node (ref "RN14") (pin "9") (pinfunction "9_9") (pintype "passive"))
      (node (ref "U4") (pin "12") (pinfunction "I7_12") (pintype "input"))
    )
    (net (code "14") (name "/~{CBR}") (class "Default")
      (node (ref "0") (pin "12") (pinfunction "~{CBR}_12") (pintype "bidirectional"))
      (node (ref "1") (pin "12") (pinfunction "~{CBR}_12") (pintype "bidirectional"))
      (node (ref "2") (pin "12") (pinfunction "~{CBR}_12") (pintype "bidirectional"))
      (node (ref "3") (pin "12") (pinfunction "~{CBR}_12") (pintype "bidirectional"))
      (node (ref "4") (pin "12") (pinfunction "~{CBR}_12") (pintype "bidirectional"))
      (node (ref "5") (pin "12") (pinfunction "~{CBR}_12") (pintype "bidirectional"))
      (node (ref "6") (pin "12") (pinfunction "~{CBR}_12") (pintype "bidirectional"))
      (node (ref "7") (pin "12") (pinfunction "~{CBR}_12") (pintype "bidirectional"))
      (node (ref "R1") (pin "2") (pinfunction "2_2") (pintype "passive"))
      (node (ref "R2") (pin "2") (pinfunction "2_2") (pintype "passive"))
      (node (ref "R4") (pin "2") (pinfunction "2_2") (pintype "passive"))
    )
    (net (code "15") (name "/~{CINH}") (class "Default")
      (node (ref "0") (pin "13") (pinfunction "~{CINH}_13") (pintype "bidirectional"))
      (node (ref "1") (pin "13") (pinfunction "~{CINH}_13") (pintype "bidirectional"))
      (node (ref "2") (pin "13") (pinfunction "~{CINH}_13") (pintype "bidirectional"))
      (node (ref "3") (pin "13") (pinfunction "~{CINH}_13") (pintype "bidirectional"))
      (node (ref "4") (pin "13") (pinfunction "~{CINH}_13") (pintype "bidirectional"))
      (node (ref "5") (pin "13") (pinfunction "~{CINH}_13") (pintype "bidirectional"))
      (node (ref "6") (pin "13") (pinfunction "~{CINH}_13") (pintype "bidirectional"))
      (node (ref "7") (pin "13") (pinfunction "~{CINH}_13") (pintype "bidirectional"))
      (node (ref "R3") (pin "2") (pinfunction "2_2") (pintype "passive"))
      (node (ref "RN10") (pin "2") (pinfunction "2_2") (pintype "passive"))
      (node (ref "RN4") (pin "2") (pinfunction "2_2") (pintype "passive"))
    )
    (net (code "16") (name "/~{CS0}") (class "Default")
      (node (ref "0") (pin "9") (pinfunction "~{CSX}_9") (pintype "bidirectional"))
      (node (ref "U7") (pin "15") (pinfunction "Y0_15") (pintype "output"))
    )
    (net (code "17") (name "/~{CS1}") (class "Default")
      (node (ref "1") (pin "9") (pinfunction "~{CSX}_9") (pintype "bidirectional"))
      (node (ref "U7") (pin "14") (pinfunction "Y1_14") (pintype "output"))
    )
    (net (code "18") (name "/~{CS2}") (class "Default")
      (node (ref "2") (pin "9") (pinfunction "~{CSX}_9") (pintype "bidirectional"))
      (node (ref "U7") (pin "13") (pinfunction "Y2_13") (pintype "output"))
    )
    (net (code "19") (name "/~{CS3}") (class "Default")
      (node (ref "3") (pin "9") (pinfunction "~{CSX}_9") (pintype "bidirectional"))
      (node (ref "U7") (pin "12") (pinfunction "Y3_12") (pintype "output"))
    )
    (net (code "20") (name "/~{CS4}") (class "Default")
      (node (ref "4") (pin "9") (pinfunction "~{CSX}_9") (pintype "bidirectional"))
      (node (ref "U7") (pin "11") (pinfunction "Y4_11") (pintype "output"))
    )
    (net (code "21") (name "/~{CS5}") (class "Default")
      (node (ref "5") (pin "9") (pinfunction "~{CSX}_9") (pintype "bidirectional"))
      (node (ref "U7") (pin "10") (pinfunction "Y5_10") (pintype "output"))
    )
    (net (code "22") (name "/~{CS6}") (class "Default")
      (node (ref "6") (pin "9") (pinfunction "~{CSX}_9") (pintype "bidirectional"))
      (node (ref "U7") (pin "9") (pinfunction "Y6_9") (pintype "output"))
    )
    (net (code "23") (name "/~{CS7}") (class "Default")
      (node (ref "7") (pin "9") (pinfunction "~{CSX}_9") (pintype "bidirectional"))
      (node (ref "U7") (pin "7") (pinfunction "Y7_7") (pintype "output"))
    )
    (net (code "24") (name "/~{FETCH}") (class "Default")
      (node (ref "0") (pin "19") (pinfunction "~{FETCH}_19") (pintype "bidirectional"))
      (node (ref "1") (pin "19") (pinfunction "~{FETCH}_19") (pintype "bidirectional"))
      (node (ref "2") (pin "19") (pinfunction "~{FETCH}_19") (pintype "bidirectional"))
      (node (ref "3") (pin "19") (pinfunction "~{FETCH}_19") (pintype "bidirectional"))
      (node (ref "4") (pin "19") (pinfunction "~{FETCH}_19") (pintype "bidirectional"))
      (node (ref "5") (pin "19") (pinfunction "~{FETCH}_19") (pintype "bidirectional"))
      (node (ref "6") (pin "19") (pinfunction "~{FETCH}_19") (pintype "bidirectional"))
      (node (ref "7") (pin "19") (pinfunction "~{FETCH}_19") (pintype "bidirectional"))
      (node (ref "RN10") (pin "5") (pinfunction "5_5") (pintype "passive"))
      (node (ref "RN4") (pin "5") (pinfunction "5_5") (pintype "passive"))
    )
    (net (code "25") (name "/~{HALT}") (class "Default")
      (node (ref "0") (pin "17") (pinfunction "~{HALT}_17") (pintype "bidirectional"))
      (node (ref "1") (pin "17") (pinfunction "~{HALT}_17") (pintype "bidirectional"))
      (node (ref "2") (pin "17") (pinfunction "~{HALT}_17") (pintype "bidirectional"))
      (node (ref "3") (pin "17") (pinfunction "~{HALT}_17") (pintype "bidirectional"))
      (node (ref "4") (pin "17") (pinfunction "~{HALT}_17") (pintype "bidirectional"))
      (node (ref "5") (pin "17") (pinfunction "~{HALT}_17") (pintype "bidirectional"))
      (node (ref "6") (pin "17") (pinfunction "~{HALT}_17") (pintype "bidirectional"))
      (node (ref "7") (pin "17") (pinfunction "~{HALT}_17") (pintype "bidirectional"))
      (node (ref "RN10") (pin "4") (pinfunction "4_4") (pintype "passive"))
      (node (ref "RN4") (pin "4") (pinfunction "4_4") (pintype "passive"))
    )
    (net (code "26") (name "/~{INH0}") (class "Default")
      (node (ref "0") (pin "11") (pinfunction "~{INH}_11") (pintype "bidirectional"))
      (node (ref "RN13") (pin "2") (pinfunction "2_2") (pintype "passive"))
      (node (ref "U3") (pin "1") (pinfunction "I0_1") (pintype "input"))
    )
    (net (code "27") (name "/~{INH1}") (class "Default")
      (node (ref "1") (pin "11") (pinfunction "~{INH}_11") (pintype "bidirectional"))
      (node (ref "RN13") (pin "3") (pinfunction "3_3") (pintype "passive"))
      (node (ref "U3") (pin "2") (pinfunction "I1_2") (pintype "input"))
    )
    (net (code "28") (name "/~{INH2}") (class "Default")
      (node (ref "2") (pin "11") (pinfunction "~{INH}_11") (pintype "bidirectional"))
      (node (ref "RN13") (pin "4") (pinfunction "4_4") (pintype "passive"))
      (node (ref "U3") (pin "3") (pinfunction "I2_3") (pintype "input"))
    )
    (net (code "29") (name "/~{INH3}") (class "Default")
      (node (ref "3") (pin "11") (pinfunction "~{INH}_11") (pintype "bidirectional"))
      (node (ref "RN13") (pin "5") (pinfunction "5_5") (pintype "passive"))
      (node (ref "U3") (pin "4") (pinfunction "I3_4") (pintype "input"))
    )
    (net (code "30") (name "/~{INH4}") (class "Default")
      (node (ref "4") (pin "11") (pinfunction "~{INH}_11") (pintype "bidirectional"))
      (node (ref "RN13") (pin "6") (pinfunction "6_6") (pintype "passive"))
      (node (ref "U3") (pin "5") (pinfunction "I4_5") (pintype "input"))
    )
    (net (code "31") (name "/~{INH5}") (class "Default")
      (node (ref "5") (pin "11") (pinfunction "~{INH}_11") (pintype "bidirectional"))
      (node (ref "RN13") (pin "7") (pinfunction "7_7") (pintype "passive"))
      (node (ref "U3") (pin "6") (pinfunction "I5_6") (pintype "input"))
    )
    (net (code "32") (name "/~{INH6}") (class "Default")
      (node (ref "6") (pin "11") (pinfunction "~{INH}_11") (pintype "bidirectional"))
      (node (ref "RN13") (pin "8") (pinfunction "8_8") (pintype "passive"))
      (node (ref "U3") (pin "11") (pinfunction "I6_11") (pintype "input"))
    )
    (net (code "33") (name "/~{INH7}") (class "Default")
      (node (ref "7") (pin "11") (pinfunction "~{INH}_11") (pintype "bidirectional"))
      (node (ref "RN13") (pin "9") (pinfunction "9_9") (pintype "passive"))
      (node (ref "U3") (pin "12") (pinfunction "I7_12") (pintype "input"))
    )
    (net (code "34") (name "/~{INHPCS}") (class "Default")
      (node (ref "U1") (pin "2") (pinfunction "I1_2") (pintype "input"))
      (node (ref "U7") (pin "5") (pinfunction "G2B_5") (pintype "input"))
      (node (ref "U8") (pin "19") (pinfunction "P=Q_19") (pintype "output"))
    )
    (net (code "35") (name "/~{INT}") (class "Default")
      (node (ref "0") (pin "51") (pinfunction "~{INT}_51") (pintype "bidirectional"))
      (node (ref "1") (pin "51") (pinfunction "~{INT}_51") (pintype "bidirectional"))
      (node (ref "2") (pin "51") (pinfunction "~{INT}_51") (pintype "bidirectional"))
      (node (ref "3") (pin "51") (pinfunction "~{INT}_51") (pintype "bidirectional"))
      (node (ref "4") (pin "51") (pinfunction "~{INT}_51") (pintype "bidirectional"))
      (node (ref "5") (pin "51") (pinfunction "~{INT}_51") (pintype "bidirectional"))
      (node (ref "6") (pin "51") (pinfunction "~{INT}_51") (pintype "bidirectional"))
      (node (ref "7") (pin "51") (pinfunction "~{INT}_51") (pintype "bidirectional"))
      (node (ref "RN12") (pin "6") (pinfunction "6_6") (pintype "passive"))
      (node (ref "RN6") (pin "6") (pinfunction "6_6") (pintype "passive"))
    )
    (net (code "36") (name "/~{IRQ0}") (class "Default")
      (node (ref "0") (pin "52") (pinfunction "~{IRQX}_52") (pintype "bidirectional"))
      (node (ref "0") (pin "53") (pinfunction "~{IRQ0}_53") (pintype "bidirectional"))
      (node (ref "1") (pin "53") (pinfunction "~{IRQ0}_53") (pintype "bidirectional"))
      (node (ref "2") (pin "53") (pinfunction "~{IRQ0}_53") (pintype "bidirectional"))
      (node (ref "3") (pin "53") (pinfunction "~{IRQ0}_53") (pintype "bidirectional"))
      (node (ref "4") (pin "53") (pinfunction "~{IRQ0}_53") (pintype "bidirectional"))
      (node (ref "5") (pin "53") (pinfunction "~{IRQ0}_53") (pintype "bidirectional"))
      (node (ref "6") (pin "53") (pinfunction "~{IRQ0}_53") (pintype "bidirectional"))
      (node (ref "7") (pin "53") (pinfunction "~{IRQ0}_53") (pintype "bidirectional"))
      (node (ref "RN3") (pin "6") (pinfunction "6_6") (pintype "passive"))
      (node (ref "RN9") (pin "6") (pinfunction "6_6") (pintype "passive"))
    )
    (net (code "37") (name "/~{IRQ1}") (class "Default")
      (node (ref "0") (pin "54") (pinfunction "~{IRQ1}_54") (pintype "bidirectional"))
      (node (ref "1") (pin "52") (pinfunction "~{IRQX}_52") (pintype "bidirectional"))
      (node (ref "1") (pin "54") (pinfunction "~{IRQ1}_54") (pintype "bidirectional"))
      (node (ref "2") (pin "54") (pinfunction "~{IRQ1}_54") (pintype "bidirectional"))
      (node (ref "3") (pin "54") (pinfunction "~{IRQ1}_54") (pintype "bidirectional"))
      (node (ref "4") (pin "54") (pinfunction "~{IRQ1}_54") (pintype "bidirectional"))
      (node (ref "5") (pin "54") (pinfunction "~{IRQ1}_54") (pintype "bidirectional"))
      (node (ref "6") (pin "54") (pinfunction "~{IRQ1}_54") (pintype "bidirectional"))
      (node (ref "7") (pin "54") (pinfunction "~{IRQ1}_54") (pintype "bidirectional"))
      (node (ref "RN12") (pin "5") (pinfunction "5_5") (pintype "passive"))
      (node (ref "RN6") (pin "5") (pinfunction "5_5") (pintype "passive"))
    )
    (net (code "38") (name "/~{IRQ2}") (class "Default")
      (node (ref "0") (pin "55") (pinfunction "~{IRQ2}_55") (pintype "bidirectional"))
      (node (ref "1") (pin "55") (pinfunction "~{IRQ2}_55") (pintype "bidirectional"))
      (node (ref "2") (pin "52") (pinfunction "~{IRQX}_52") (pintype "bidirectional"))
      (node (ref "2") (pin "55") (pinfunction "~{IRQ2}_55") (pintype "bidirectional"))
      (node (ref "3") (pin "55") (pinfunction "~{IRQ2}_55") (pintype "bidirectional"))
      (node (ref "4") (pin "55") (pinfunction "~{IRQ2}_55") (pintype "bidirectional"))
      (node (ref "5") (pin "55") (pinfunction "~{IRQ2}_55") (pintype "bidirectional"))
      (node (ref "6") (pin "55") (pinfunction "~{IRQ2}_55") (pintype "bidirectional"))
      (node (ref "7") (pin "55") (pinfunction "~{IRQ2}_55") (pintype "bidirectional"))
      (node (ref "RN3") (pin "5") (pinfunction "5_5") (pintype "passive"))
      (node (ref "RN9") (pin "5") (pinfunction "5_5") (pintype "passive"))
    )
    (net (code "39") (name "/~{IRQ3}") (class "Default")
      (node (ref "0") (pin "56") (pinfunction "~{IRQ3}_56") (pintype "bidirectional"))
      (node (ref "1") (pin "56") (pinfunction "~{IRQ3}_56") (pintype "bidirectional"))
      (node (ref "2") (pin "56") (pinfunction "~{IRQ3}_56") (pintype "bidirectional"))
      (node (ref "3") (pin "52") (pinfunction "~{IRQX}_52") (pintype "bidirectional"))
      (node (ref "3") (pin "56") (pinfunction "~{IRQ3}_56") (pintype "bidirectional"))
      (node (ref "4") (pin "56") (pinfunction "~{IRQ3}_56") (pintype "bidirectional"))
      (node (ref "5") (pin "56") (pinfunction "~{IRQ3}_56") (pintype "bidirectional"))
      (node (ref "6") (pin "56") (pinfunction "~{IRQ3}_56") (pintype "bidirectional"))
      (node (ref "7") (pin "56") (pinfunction "~{IRQ3}_56") (pintype "bidirectional"))
      (node (ref "RN12") (pin "4") (pinfunction "4_4") (pintype "passive"))
      (node (ref "RN6") (pin "4") (pinfunction "4_4") (pintype "passive"))
    )
    (net (code "40") (name "/~{IRQ4}") (class "Default")
      (node (ref "0") (pin "57") (pinfunction "~{IRQ4}_57") (pintype "bidirectional"))
      (node (ref "1") (pin "57") (pinfunction "~{IRQ4}_57") (pintype "bidirectional"))
      (node (ref "2") (pin "57") (pinfunction "~{IRQ4}_57") (pintype "bidirectional"))
      (node (ref "3") (pin "57") (pinfunction "~{IRQ4}_57") (pintype "bidirectional"))
      (node (ref "4") (pin "52") (pinfunction "~{IRQX}_52") (pintype "bidirectional"))
      (node (ref "4") (pin "57") (pinfunction "~{IRQ4}_57") (pintype "bidirectional"))
      (node (ref "5") (pin "57") (pinfunction "~{IRQ4}_57") (pintype "bidirectional"))
      (node (ref "6") (pin "57") (pinfunction "~{IRQ4}_57") (pintype "bidirectional"))
      (node (ref "7") (pin "57") (pinfunction "~{IRQ4}_57") (pintype "bidirectional"))
      (node (ref "RN3") (pin "4") (pinfunction "4_4") (pintype "passive"))
      (node (ref "RN9") (pin "4") (pinfunction "4_4") (pintype "passive"))
    )
    (net (code "41") (name "/~{IRQ5}") (class "Default")
      (node (ref "0") (pin "58") (pinfunction "~{IRQ5}_58") (pintype "bidirectional"))
      (node (ref "1") (pin "58") (pinfunction "~{IRQ5}_58") (pintype "bidirectional"))
      (node (ref "2") (pin "58") (pinfunction "~{IRQ5}_58") (pintype "bidirectional"))
      (node (ref "3") (pin "58") (pinfunction "~{IRQ5}_58") (pintype "bidirectional"))
      (node (ref "4") (pin "58") (pinfunction "~{IRQ5}_58") (pintype "bidirectional"))
      (node (ref "5") (pin "52") (pinfunction "~{IRQX}_52") (pintype "bidirectional"))
      (node (ref "5") (pin "58") (pinfunction "~{IRQ5}_58") (pintype "bidirectional"))
      (node (ref "6") (pin "58") (pinfunction "~{IRQ5}_58") (pintype "bidirectional"))
      (node (ref "7") (pin "58") (pinfunction "~{IRQ5}_58") (pintype "bidirectional"))
      (node (ref "RN12") (pin "3") (pinfunction "3_3") (pintype "passive"))
      (node (ref "RN6") (pin "3") (pinfunction "3_3") (pintype "passive"))
    )
    (net (code "42") (name "/~{IRQ6}") (class "Default")
      (node (ref "0") (pin "59") (pinfunction "~{IRQ6}_59") (pintype "bidirectional"))
      (node (ref "1") (pin "59") (pinfunction "~{IRQ6}_59") (pintype "bidirectional"))
      (node (ref "2") (pin "59") (pinfunction "~{IRQ6}_59") (pintype "bidirectional"))
      (node (ref "3") (pin "59") (pinfunction "~{IRQ6}_59") (pintype "bidirectional"))
      (node (ref "4") (pin "59") (pinfunction "~{IRQ6}_59") (pintype "bidirectional"))
      (node (ref "5") (pin "59") (pinfunction "~{IRQ6}_59") (pintype "bidirectional"))
      (node (ref "6") (pin "52") (pinfunction "~{IRQX}_52") (pintype "bidirectional"))
      (node (ref "6") (pin "59") (pinfunction "~{IRQ6}_59") (pintype "bidirectional"))
      (node (ref "7") (pin "59") (pinfunction "~{IRQ6}_59") (pintype "bidirectional"))
      (node (ref "RN3") (pin "3") (pinfunction "3_3") (pintype "passive"))
      (node (ref "RN9") (pin "3") (pinfunction "3_3") (pintype "passive"))
    )
    (net (code "43") (name "/~{IRQ7}") (class "Default")
      (node (ref "0") (pin "60") (pinfunction "~{IRQ7}_60") (pintype "bidirectional"))
      (node (ref "1") (pin "60") (pinfunction "~{IRQ7}_60") (pintype "bidirectional"))
      (node (ref "2") (pin "60") (pinfunction "~{IRQ7}_60") (pintype "bidirectional"))
      (node (ref "3") (pin "60") (pinfunction "~{IRQ7}_60") (pintype "bidirectional"))
      (node (ref "4") (pin "60") (pinfunction "~{IRQ7}_60") (pintype "bidirectional"))
      (node (ref "5") (pin "60") (pinfunction "~{IRQ7}_60") (pintype "bidirectional"))
      (node (ref "6") (pin "60") (pinfunction "~{IRQ7}_60") (pintype "bidirectional"))
      (node (ref "7") (pin "52") (pinfunction "~{IRQX}_52") (pintype "bidirectional"))
      (node (ref "7") (pin "60") (pinfunction "~{IRQ7}_60") (pintype "bidirectional"))
      (node (ref "RN12") (pin "2") (pinfunction "2_2") (pintype "passive"))
      (node (ref "RN6") (pin "2") (pinfunction "2_2") (pintype "passive"))
    )
    (net (code "44") (name "/~{NMI}") (class "Default")
      (node (ref "0") (pin "61") (pinfunction "~{NMI}_61") (pintype "bidirectional"))
      (node (ref "1") (pin "61") (pinfunction "~{NMI}_61") (pintype "bidirectional"))
      (node (ref "2") (pin "61") (pinfunction "~{NMI}_61") (pintype "bidirectional"))
      (node (ref "3") (pin "61") (pinfunction "~{NMI}_61") (pintype "bidirectional"))
      (node (ref "4") (pin "61") (pinfunction "~{NMI}_61") (pintype "bidirectional"))
      (node (ref "5") (pin "61") (pinfunction "~{NMI}_61") (pintype "bidirectional"))
      (node (ref "6") (pin "61") (pinfunction "~{NMI}_61") (pintype "bidirectional"))
      (node (ref "7") (pin "61") (pinfunction "~{NMI}_61") (pintype "bidirectional"))
      (node (ref "RN3") (pin "2") (pinfunction "2_2") (pintype "passive"))
      (node (ref "RN9") (pin "2") (pinfunction "2_2") (pintype "passive"))
    )
    (net (code "45") (name "/~{RD}") (class "Default")
      (node (ref "0") (pin "21") (pinfunction "~{RD}_21") (pintype "bidirectional"))
      (node (ref "1") (pin "21") (pinfunction "~{RD}_21") (pintype "bidirectional"))
      (node (ref "2") (pin "21") (pinfunction "~{RD}_21") (pintype "bidirectional"))
      (node (ref "3") (pin "21") (pinfunction "~{RD}_21") (pintype "bidirectional"))
      (node (ref "4") (pin "21") (pinfunction "~{RD}_21") (pintype "bidirectional"))
      (node (ref "5") (pin "21") (pinfunction "~{RD}_21") (pintype "bidirectional"))
      (node (ref "6") (pin "21") (pinfunction "~{RD}_21") (pintype "bidirectional"))
      (node (ref "7") (pin "21") (pinfunction "~{RD}_21") (pintype "bidirectional"))
      (node (ref "RN10") (pin "6") (pinfunction "6_6") (pintype "passive"))
      (node (ref "RN4") (pin "6") (pinfunction "6_6") (pintype "passive"))
    )
    (net (code "46") (name "/~{RST}") (class "Default")
      (node (ref "0") (pin "14") (pinfunction "~{RST}_14") (pintype "bidirectional"))
      (node (ref "1") (pin "14") (pinfunction "~{RST}_14") (pintype "bidirectional"))
      (node (ref "2") (pin "14") (pinfunction "~{RST}_14") (pintype "bidirectional"))
      (node (ref "3") (pin "14") (pinfunction "~{RST}_14") (pintype "bidirectional"))
      (node (ref "4") (pin "14") (pinfunction "~{RST}_14") (pintype "bidirectional"))
      (node (ref "5") (pin "14") (pinfunction "~{RST}_14") (pintype "bidirectional"))
      (node (ref "6") (pin "14") (pinfunction "~{RST}_14") (pintype "bidirectional"))
      (node (ref "7") (pin "14") (pinfunction "~{RST}_14") (pintype "bidirectional"))
      (node (ref "JP7") (pin "2") (pinfunction "2_2") (pintype "passive"))
      (node (ref "R10") (pin "1") (pinfunction "1_1") (pintype "passive"))
      (node (ref "RN1") (pin "2") (pinfunction "2_2") (pintype "passive"))
      (node (ref "RN7") (pin "2") (pinfunction "2_2") (pintype "passive"))
    )
    (net (code "47") (name "/~{WAIT}") (class "Default")
      (node (ref "0") (pin "18") (pinfunction "~{WAIT}_18") (pintype "bidirectional"))
      (node (ref "1") (pin "18") (pinfunction "~{WAIT}_18") (pintype "bidirectional"))
      (node (ref "2") (pin "18") (pinfunction "~{WAIT}_18") (pintype "bidirectional"))
      (node (ref "3") (pin "18") (pinfunction "~{WAIT}_18") (pintype "bidirectional"))
      (node (ref "4") (pin "18") (pinfunction "~{WAIT}_18") (pintype "bidirectional"))
      (node (ref "5") (pin "18") (pinfunction "~{WAIT}_18") (pintype "bidirectional"))
      (node (ref "6") (pin "18") (pinfunction "~{WAIT}_18") (pintype "bidirectional"))
      (node (ref "7") (pin "18") (pinfunction "~{WAIT}_18") (pintype "bidirectional"))
      (node (ref "RN1") (pin "4") (pinfunction "4_4") (pintype "passive"))
      (node (ref "RN7") (pin "4") (pinfunction "4_4") (pintype "passive"))
    )
    (net (code "48") (name "/~{WR}") (class "Default")
      (node (ref "0") (pin "22") (pinfunction "~{WR}_22") (pintype "bidirectional"))
      (node (ref "1") (pin "22") (pinfunction "~{WR}_22") (pintype "bidirectional"))
      (node (ref "2") (pin "22") (pinfunction "~{WR}_22") (pintype "bidirectional"))
      (node (ref "3") (pin "22") (pinfunction "~{WR}_22") (pintype "bidirectional"))
      (node (ref "4") (pin "22") (pinfunction "~{WR}_22") (pintype "bidirectional"))
      (node (ref "5") (pin "22") (pinfunction "~{WR}_22") (pintype "bidirectional"))
      (node (ref "6") (pin "22") (pinfunction "~{WR}_22") (pintype "bidirectional"))
      (node (ref "7") (pin "22") (pinfunction "~{WR}_22") (pintype "bidirectional"))
      (node (ref "RN1") (pin "6") (pinfunction "6_6") (pintype "passive"))
      (node (ref "RN7") (pin "6") (pinfunction "6_6") (pintype "passive"))
    )
    (net (code "49") (name "A0") (class "Default")
      (node (ref "0") (pin "23") (pinfunction "A0_23") (pintype "bidirectional"))
      (node (ref "1") (pin "23") (pinfunction "A0_23") (pintype "bidirectional"))
      (node (ref "2") (pin "23") (pinfunction "A0_23") (pintype "bidirectional"))
      (node (ref "3") (pin "23") (pinfunction "A0_23") (pintype "bidirectional"))
      (node (ref "4") (pin "23") (pinfunction "A0_23") (pintype "bidirectional"))
      (node (ref "5") (pin "23") (pinfunction "A0_23") (pintype "bidirectional"))
      (node (ref "6") (pin "23") (pinfunction "A0_23") (pintype "bidirectional"))
      (node (ref "7") (pin "23") (pinfunction "A0_23") (pintype "bidirectional"))
      (node (ref "RN10") (pin "7") (pinfunction "7_7") (pintype "passive"))
      (node (ref "RN4") (pin "7") (pinfunction "7_7") (pintype "passive"))
    )
    (net (code "50") (name "A1") (class "Default")
      (node (ref "0") (pin "24") (pinfunction "A1_24") (pintype "bidirectional"))
      (node (ref "1") (pin "24") (pinfunction "A1_24") (pintype "bidirectional"))
      (node (ref "2") (pin "24") (pinfunction "A1_24") (pintype "bidirectional"))
      (node (ref "3") (pin "24") (pinfunction "A1_24") (pintype "bidirectional"))
      (node (ref "4") (pin "24") (pinfunction "A1_24") (pintype "bidirectional"))
      (node (ref "5") (pin "24") (pinfunction "A1_24") (pintype "bidirectional"))
      (node (ref "6") (pin "24") (pinfunction "A1_24") (pintype "bidirectional"))
      (node (ref "7") (pin "24") (pinfunction "A1_24") (pintype "bidirectional"))
      (node (ref "RN1") (pin "7") (pinfunction "7_7") (pintype "passive"))
      (node (ref "RN7") (pin "7") (pinfunction "7_7") (pintype "passive"))
    )
    (net (code "51") (name "A2") (class "Default")
      (node (ref "0") (pin "25") (pinfunction "A2_25") (pintype "bidirectional"))
      (node (ref "1") (pin "25") (pinfunction "A2_25") (pintype "bidirectional"))
      (node (ref "2") (pin "25") (pinfunction "A2_25") (pintype "bidirectional"))
      (node (ref "3") (pin "25") (pinfunction "A2_25") (pintype "bidirectional"))
      (node (ref "4") (pin "25") (pinfunction "A2_25") (pintype "bidirectional"))
      (node (ref "5") (pin "25") (pinfunction "A2_25") (pintype "bidirectional"))
      (node (ref "6") (pin "25") (pinfunction "A2_25") (pintype "bidirectional"))
      (node (ref "7") (pin "25") (pinfunction "A2_25") (pintype "bidirectional"))
      (node (ref "RN10") (pin "8") (pinfunction "8_8") (pintype "passive"))
      (node (ref "RN4") (pin "8") (pinfunction "8_8") (pintype "passive"))
    )
    (net (code "52") (name "A3") (class "Default")
      (node (ref "0") (pin "26") (pinfunction "A3_26") (pintype "bidirectional"))
      (node (ref "1") (pin "26") (pinfunction "A3_26") (pintype "bidirectional"))
      (node (ref "2") (pin "26") (pinfunction "A3_26") (pintype "bidirectional"))
      (node (ref "3") (pin "26") (pinfunction "A3_26") (pintype "bidirectional"))
      (node (ref "4") (pin "26") (pinfunction "A3_26") (pintype "bidirectional"))
      (node (ref "5") (pin "26") (pinfunction "A3_26") (pintype "bidirectional"))
      (node (ref "6") (pin "26") (pinfunction "A3_26") (pintype "bidirectional"))
      (node (ref "7") (pin "26") (pinfunction "A3_26") (pintype "bidirectional"))
      (node (ref "RN1") (pin "8") (pinfunction "8_8") (pintype "passive"))
      (node (ref "RN7") (pin "8") (pinfunction "8_8") (pintype "passive"))
    )
    (net (code "53") (name "A4") (class "Default")
      (node (ref "0") (pin "27") (pinfunction "A4_27") (pintype "bidirectional"))
      (node (ref "1") (pin "27") (pinfunction "A4_27") (pintype "bidirectional"))
      (node (ref "2") (pin "27") (pinfunction "A4_27") (pintype "bidirectional"))
      (node (ref "3") (pin "27") (pinfunction "A4_27") (pintype "bidirectional"))
      (node (ref "4") (pin "27") (pinfunction "A4_27") (pintype "bidirectional"))
      (node (ref "5") (pin "27") (pinfunction "A4_27") (pintype "bidirectional"))
      (node (ref "6") (pin "27") (pinfunction "A4_27") (pintype "bidirectional"))
      (node (ref "7") (pin "27") (pinfunction "A4_27") (pintype "bidirectional"))
      (node (ref "RN10") (pin "9") (pinfunction "9_9") (pintype "passive"))
      (node (ref "RN4") (pin "9") (pinfunction "9_9") (pintype "passive"))
    )
    (net (code "54") (name "A5") (class "Default")
      (node (ref "0") (pin "28") (pinfunction "A5_28") (pintype "bidirectional"))
      (node (ref "1") (pin "28") (pinfunction "A5_28") (pintype "bidirectional"))
      (node (ref "2") (pin "28") (pinfunction "A5_28") (pintype "bidirectional"))
      (node (ref "3") (pin "28") (pinfunction "A5_28") (pintype "bidirectional"))
      (node (ref "4") (pin "28") (pinfunction "A5_28") (pintype "bidirectional"))
      (node (ref "5") (pin "28") (pinfunction "A5_28") (pintype "bidirectional"))
      (node (ref "6") (pin "28") (pinfunction "A5_28") (pintype "bidirectional"))
      (node (ref "7") (pin "28") (pinfunction "A5_28") (pintype "bidirectional"))
      (node (ref "RN1") (pin "9") (pinfunction "9_9") (pintype "passive"))
      (node (ref "RN7") (pin "9") (pinfunction "9_9") (pintype "passive"))
    )
    (net (code "55") (name "A6") (class "Default")
      (node (ref "0") (pin "29") (pinfunction "A6_29") (pintype "bidirectional"))
      (node (ref "1") (pin "29") (pinfunction "A6_29") (pintype "bidirectional"))
      (node (ref "2") (pin "29") (pinfunction "A6_29") (pintype "bidirectional"))
      (node (ref "3") (pin "29") (pinfunction "A6_29") (pintype "bidirectional"))
      (node (ref "4") (pin "29") (pinfunction "A6_29") (pintype "bidirectional"))
      (node (ref "5") (pin "29") (pinfunction "A6_29") (pintype "bidirectional"))
      (node (ref "6") (pin "29") (pinfunction "A6_29") (pintype "bidirectional"))
      (node (ref "7") (pin "29") (pinfunction "A6_29") (pintype "bidirectional"))
      (node (ref "RN11") (pin "2") (pinfunction "2_2") (pintype "passive"))
      (node (ref "RN5") (pin "2") (pinfunction "2_2") (pintype "passive"))
    )
    (net (code "56") (name "A7") (class "Default")
      (node (ref "0") (pin "30") (pinfunction "A7_30") (pintype "bidirectional"))
      (node (ref "1") (pin "30") (pinfunction "A7_30") (pintype "bidirectional"))
      (node (ref "2") (pin "30") (pinfunction "A7_30") (pintype "bidirectional"))
      (node (ref "3") (pin "30") (pinfunction "A7_30") (pintype "bidirectional"))
      (node (ref "4") (pin "30") (pinfunction "A7_30") (pintype "bidirectional"))
      (node (ref "5") (pin "30") (pinfunction "A7_30") (pintype "bidirectional"))
      (node (ref "6") (pin "30") (pinfunction "A7_30") (pintype "bidirectional"))
      (node (ref "7") (pin "30") (pinfunction "A7_30") (pintype "bidirectional"))
      (node (ref "RN2") (pin "2") (pinfunction "2_2") (pintype "passive"))
      (node (ref "RN8") (pin "2") (pinfunction "2_2") (pintype "passive"))
    )
    (net (code "57") (name "A8") (class "Default")
      (node (ref "0") (pin "31") (pinfunction "A8_31") (pintype "bidirectional"))
      (node (ref "1") (pin "31") (pinfunction "A8_31") (pintype "bidirectional"))
      (node (ref "2") (pin "31") (pinfunction "A8_31") (pintype "bidirectional"))
      (node (ref "3") (pin "31") (pinfunction "A8_31") (pintype "bidirectional"))
      (node (ref "4") (pin "31") (pinfunction "A8_31") (pintype "bidirectional"))
      (node (ref "5") (pin "31") (pinfunction "A8_31") (pintype "bidirectional"))
      (node (ref "6") (pin "31") (pinfunction "A8_31") (pintype "bidirectional"))
      (node (ref "7") (pin "31") (pinfunction "A8_31") (pintype "bidirectional"))
      (node (ref "RN11") (pin "3") (pinfunction "3_3") (pintype "passive"))
      (node (ref "RN5") (pin "3") (pinfunction "3_3") (pintype "passive"))
      (node (ref "U7") (pin "1") (pinfunction "A_1") (pintype "input"))
    )
    (net (code "58") (name "A9") (class "Default")
      (node (ref "0") (pin "32") (pinfunction "A9_32") (pintype "bidirectional"))
      (node (ref "1") (pin "32") (pinfunction "A9_32") (pintype "bidirectional"))
      (node (ref "2") (pin "32") (pinfunction "A9_32") (pintype "bidirectional"))
      (node (ref "3") (pin "32") (pinfunction "A9_32") (pintype "bidirectional"))
      (node (ref "4") (pin "32") (pinfunction "A9_32") (pintype "bidirectional"))
      (node (ref "5") (pin "32") (pinfunction "A9_32") (pintype "bidirectional"))
      (node (ref "6") (pin "32") (pinfunction "A9_32") (pintype "bidirectional"))
      (node (ref "7") (pin "32") (pinfunction "A9_32") (pintype "bidirectional"))
      (node (ref "RN2") (pin "3") (pinfunction "3_3") (pintype "passive"))
      (node (ref "RN8") (pin "3") (pinfunction "3_3") (pintype "passive"))
      (node (ref "U7") (pin "2") (pinfunction "B_2") (pintype "input"))
    )
    (net (code "59") (name "A10") (class "Default")
      (node (ref "0") (pin "33") (pinfunction "A10_33") (pintype "bidirectional"))
      (node (ref "1") (pin "33") (pinfunction "A10_33") (pintype "bidirectional"))
      (node (ref "2") (pin "33") (pinfunction "A10_33") (pintype "bidirectional"))
      (node (ref "3") (pin "33") (pinfunction "A10_33") (pintype "bidirectional"))
      (node (ref "4") (pin "33") (pinfunction "A10_33") (pintype "bidirectional"))
      (node (ref "5") (pin "33") (pinfunction "A10_33") (pintype "bidirectional"))
      (node (ref "6") (pin "33") (pinfunction "A10_33") (pintype "bidirectional"))
      (node (ref "7") (pin "33") (pinfunction "A10_33") (pintype "bidirectional"))
      (node (ref "RN11") (pin "4") (pinfunction "4_4") (pintype "passive"))
      (node (ref "RN5") (pin "4") (pinfunction "4_4") (pintype "passive"))
      (node (ref "U7") (pin "3") (pinfunction "C_3") (pintype "input"))
    )
    (net (code "60") (name "A11") (class "Default")
      (node (ref "0") (pin "34") (pinfunction "A11_34") (pintype "bidirectional"))
      (node (ref "1") (pin "34") (pinfunction "A11_34") (pintype "bidirectional"))
      (node (ref "2") (pin "34") (pinfunction "A11_34") (pintype "bidirectional"))
      (node (ref "3") (pin "34") (pinfunction "A11_34") (pintype "bidirectional"))
      (node (ref "4") (pin "34") (pinfunction "A11_34") (pintype "bidirectional"))
      (node (ref "5") (pin "34") (pinfunction "A11_34") (pintype "bidirectional"))
      (node (ref "6") (pin "34") (pinfunction "A11_34") (pintype "bidirectional"))
      (node (ref "7") (pin "34") (pinfunction "A11_34") (pintype "bidirectional"))
      (node (ref "RN2") (pin "4") (pinfunction "4_4") (pintype "passive"))
      (node (ref "RN8") (pin "4") (pinfunction "4_4") (pintype "passive"))
      (node (ref "U7") (pin "4") (pinfunction "G2A_4") (pintype "input"))
    )
    (net (code "61") (name "A12") (class "Default")
      (node (ref "0") (pin "35") (pinfunction "A12_35") (pintype "bidirectional"))
      (node (ref "1") (pin "35") (pinfunction "A12_35") (pintype "bidirectional"))
      (node (ref "2") (pin "35") (pinfunction "A12_35") (pintype "bidirectional"))
      (node (ref "3") (pin "35") (pinfunction "A12_35") (pintype "bidirectional"))
      (node (ref "4") (pin "35") (pinfunction "A12_35") (pintype "bidirectional"))
      (node (ref "5") (pin "35") (pinfunction "A12_35") (pintype "bidirectional"))
      (node (ref "6") (pin "35") (pinfunction "A12_35") (pintype "bidirectional"))
      (node (ref "7") (pin "35") (pinfunction "A12_35") (pintype "bidirectional"))
      (node (ref "RN11") (pin "5") (pinfunction "5_5") (pintype "passive"))
      (node (ref "RN5") (pin "5") (pinfunction "5_5") (pintype "passive"))
      (node (ref "U8") (pin "2") (pinfunction "P0_2") (pintype "input"))
    )
    (net (code "62") (name "A13") (class "Default")
      (node (ref "0") (pin "36") (pinfunction "A13_36") (pintype "bidirectional"))
      (node (ref "1") (pin "36") (pinfunction "A13_36") (pintype "bidirectional"))
      (node (ref "2") (pin "36") (pinfunction "A13_36") (pintype "bidirectional"))
      (node (ref "3") (pin "36") (pinfunction "A13_36") (pintype "bidirectional"))
      (node (ref "4") (pin "36") (pinfunction "A13_36") (pintype "bidirectional"))
      (node (ref "5") (pin "36") (pinfunction "A13_36") (pintype "bidirectional"))
      (node (ref "6") (pin "36") (pinfunction "A13_36") (pintype "bidirectional"))
      (node (ref "7") (pin "36") (pinfunction "A13_36") (pintype "bidirectional"))
      (node (ref "RN2") (pin "5") (pinfunction "5_5") (pintype "passive"))
      (node (ref "RN8") (pin "5") (pinfunction "5_5") (pintype "passive"))
      (node (ref "U8") (pin "17") (pinfunction "P7_17") (pintype "input"))
    )
    (net (code "63") (name "A14") (class "Default")
      (node (ref "0") (pin "37") (pinfunction "A14_37") (pintype "bidirectional"))
      (node (ref "1") (pin "37") (pinfunction "A14_37") (pintype "bidirectional"))
      (node (ref "2") (pin "37") (pinfunction "A14_37") (pintype "bidirectional"))
      (node (ref "3") (pin "37") (pinfunction "A14_37") (pintype "bidirectional"))
      (node (ref "4") (pin "37") (pinfunction "A14_37") (pintype "bidirectional"))
      (node (ref "5") (pin "37") (pinfunction "A14_37") (pintype "bidirectional"))
      (node (ref "6") (pin "37") (pinfunction "A14_37") (pintype "bidirectional"))
      (node (ref "7") (pin "37") (pinfunction "A14_37") (pintype "bidirectional"))
      (node (ref "RN11") (pin "6") (pinfunction "6_6") (pintype "passive"))
      (node (ref "RN5") (pin "6") (pinfunction "6_6") (pintype "passive"))
      (node (ref "U8") (pin "4") (pinfunction "P1_4") (pintype "input"))
    )
    (net (code "64") (name "A15") (class "Default")
      (node (ref "0") (pin "38") (pinfunction "A15_38") (pintype "bidirectional"))
      (node (ref "1") (pin "38") (pinfunction "A15_38") (pintype "bidirectional"))
      (node (ref "2") (pin "38") (pinfunction "A15_38") (pintype "bidirectional"))
      (node (ref "3") (pin "38") (pinfunction "A15_38") (pintype "bidirectional"))
      (node (ref "4") (pin "38") (pinfunction "A15_38") (pintype "bidirectional"))
      (node (ref "5") (pin "38") (pinfunction "A15_38") (pintype "bidirectional"))
      (node (ref "6") (pin "38") (pinfunction "A15_38") (pintype "bidirectional"))
      (node (ref "7") (pin "38") (pinfunction "A15_38") (pintype "bidirectional"))
      (node (ref "RN2") (pin "6") (pinfunction "6_6") (pintype "passive"))
      (node (ref "RN8") (pin "6") (pinfunction "6_6") (pintype "passive"))
      (node (ref "U8") (pin "15") (pinfunction "P6_15") (pintype "input"))
    )
    (net (code "65") (name "A16") (class "Default")
      (node (ref "0") (pin "39") (pinfunction "A16_39") (pintype "bidirectional"))
      (node (ref "1") (pin "39") (pinfunction "A16_39") (pintype "bidirectional"))
      (node (ref "2") (pin "39") (pinfunction "A16_39") (pintype "bidirectional"))
      (node (ref "3") (pin "39") (pinfunction "A16_39") (pintype "bidirectional"))
      (node (ref "4") (pin "39") (pinfunction "A16_39") (pintype "bidirectional"))
      (node (ref "5") (pin "39") (pinfunction "A16_39") (pintype "bidirectional"))
      (node (ref "6") (pin "39") (pinfunction "A16_39") (pintype "bidirectional"))
      (node (ref "7") (pin "39") (pinfunction "A16_39") (pintype "bidirectional"))
      (node (ref "RN11") (pin "7") (pinfunction "7_7") (pintype "passive"))
      (node (ref "RN5") (pin "7") (pinfunction "7_7") (pintype "passive"))
      (node (ref "U8") (pin "6") (pinfunction "P2_6") (pintype "input"))
    )
    (net (code "66") (name "A17") (class "Default")
      (node (ref "0") (pin "40") (pinfunction "A17_40") (pintype "bidirectional"))
      (node (ref "1") (pin "40") (pinfunction "A17_40") (pintype "bidirectional"))
      (node (ref "2") (pin "40") (pinfunction "A17_40") (pintype "bidirectional"))
      (node (ref "3") (pin "40") (pinfunction "A17_40") (pintype "bidirectional"))
      (node (ref "4") (pin "40") (pinfunction "A17_40") (pintype "bidirectional"))
      (node (ref "5") (pin "40") (pinfunction "A17_40") (pintype "bidirectional"))
      (node (ref "6") (pin "40") (pinfunction "A17_40") (pintype "bidirectional"))
      (node (ref "7") (pin "40") (pinfunction "A17_40") (pintype "bidirectional"))
      (node (ref "RN2") (pin "7") (pinfunction "7_7") (pintype "passive"))
      (node (ref "RN8") (pin "7") (pinfunction "7_7") (pintype "passive"))
      (node (ref "U8") (pin "13") (pinfunction "P5_13") (pintype "input"))
    )
    (net (code "67") (name "A18") (class "Default")
      (node (ref "0") (pin "41") (pinfunction "A18_41") (pintype "bidirectional"))
      (node (ref "1") (pin "41") (pinfunction "A18_41") (pintype "bidirectional"))
      (node (ref "2") (pin "41") (pinfunction "A18_41") (pintype "bidirectional"))
      (node (ref "3") (pin "41") (pinfunction "A18_41") (pintype "bidirectional"))
      (node (ref "4") (pin "41") (pinfunction "A18_41") (pintype "bidirectional"))
      (node (ref "5") (pin "41") (pinfunction "A18_41") (pintype "bidirectional"))
      (node (ref "6") (pin "41") (pinfunction "A18_41") (pintype "bidirectional"))
      (node (ref "7") (pin "41") (pinfunction "A18_41") (pintype "bidirectional"))
      (node (ref "RN11") (pin "8") (pinfunction "8_8") (pintype "passive"))
      (node (ref "RN5") (pin "8") (pinfunction "8_8") (pintype "passive"))
      (node (ref "U8") (pin "8") (pinfunction "P3_8") (pintype "input"))
    )
    (net (code "68") (name "A19") (class "Default")
      (node (ref "0") (pin "42") (pinfunction "A19_42") (pintype "bidirectional"))
      (node (ref "1") (pin "42") (pinfunction "A19_42") (pintype "bidirectional"))
      (node (ref "2") (pin "42") (pinfunction "A19_42") (pintype "bidirectional"))
      (node (ref "3") (pin "42") (pinfunction "A19_42") (pintype "bidirectional"))
      (node (ref "4") (pin "42") (pinfunction "A19_42") (pintype "bidirectional"))
      (node (ref "5") (pin "42") (pinfunction "A19_42") (pintype "bidirectional"))
      (node (ref "6") (pin "42") (pinfunction "A19_42") (pintype "bidirectional"))
      (node (ref "7") (pin "42") (pinfunction "A19_42") (pintype "bidirectional"))
      (node (ref "RN2") (pin "8") (pinfunction "8_8") (pintype "passive"))
      (node (ref "RN8") (pin "8") (pinfunction "8_8") (pintype "passive"))
      (node (ref "U8") (pin "11") (pinfunction "P4_11") (pintype "input"))
    )
    (net (code "69") (name "CKLAUX") (class "Default")
      (node (ref "0") (pin "16") (pinfunction "CLKAUX_16") (pintype "bidirectional"))
      (node (ref "1") (pin "16") (pinfunction "CLKAUX_16") (pintype "bidirectional"))
      (node (ref "2") (pin "16") (pinfunction "CLKAUX_16") (pintype "bidirectional"))
      (node (ref "3") (pin "16") (pinfunction "CLKAUX_16") (pintype "bidirectional"))
      (node (ref "4") (pin "16") (pinfunction "CLKAUX_16") (pintype "bidirectional"))
      (node (ref "5") (pin "16") (pinfunction "CLKAUX_16") (pintype "bidirectional"))
      (node (ref "6") (pin "16") (pinfunction "CLKAUX_16") (pintype "bidirectional"))
      (node (ref "7") (pin "16") (pinfunction "CLKAUX_16") (pintype "bidirectional"))
      (node (ref "RN1") (pin "3") (pinfunction "3_3") (pintype "passive"))
      (node (ref "RN7") (pin "3") (pinfunction "3_3") (pintype "passive"))
    )
    (net (code "70") (name "CLK") (class "Default")
      (node (ref "0") (pin "15") (pinfunction "CLK_15") (pintype "bidirectional"))
      (node (ref "1") (pin "15") (pinfunction "CLK_15") (pintype "bidirectional"))
      (node (ref "2") (pin "15") (pinfunction "CLK_15") (pintype "bidirectional"))
      (node (ref "3") (pin "15") (pinfunction "CLK_15") (pintype "bidirectional"))
      (node (ref "4") (pin "15") (pinfunction "CLK_15") (pintype "bidirectional"))
      (node (ref "5") (pin "15") (pinfunction "CLK_15") (pintype "bidirectional"))
      (node (ref "6") (pin "15") (pinfunction "CLK_15") (pintype "bidirectional"))
      (node (ref "7") (pin "15") (pinfunction "CLK_15") (pintype "bidirectional"))
      (node (ref "RN10") (pin "3") (pinfunction "3_3") (pintype "passive"))
      (node (ref "RN4") (pin "3") (pinfunction "3_3") (pintype "passive"))
    )
    (net (code "71") (name "D0") (class "Default")
      (node (ref "0") (pin "43") (pinfunction "D0_43") (pintype "bidirectional"))
      (node (ref "1") (pin "43") (pinfunction "D0_43") (pintype "bidirectional"))
      (node (ref "2") (pin "43") (pinfunction "D0_43") (pintype "bidirectional"))
      (node (ref "3") (pin "43") (pinfunction "D0_43") (pintype "bidirectional"))
      (node (ref "4") (pin "43") (pinfunction "D0_43") (pintype "bidirectional"))
      (node (ref "5") (pin "43") (pinfunction "D0_43") (pintype "bidirectional"))
      (node (ref "6") (pin "43") (pinfunction "D0_43") (pintype "bidirectional"))
      (node (ref "7") (pin "43") (pinfunction "D0_43") (pintype "bidirectional"))
      (node (ref "RN11") (pin "9") (pinfunction "9_9") (pintype "passive"))
      (node (ref "RN5") (pin "9") (pinfunction "9_9") (pintype "passive"))
    )
    (net (code "72") (name "D1") (class "Default")
      (node (ref "0") (pin "44") (pinfunction "D1_44") (pintype "bidirectional"))
      (node (ref "1") (pin "44") (pinfunction "D1_44") (pintype "bidirectional"))
      (node (ref "2") (pin "44") (pinfunction "D1_44") (pintype "bidirectional"))
      (node (ref "3") (pin "44") (pinfunction "D1_44") (pintype "bidirectional"))
      (node (ref "4") (pin "44") (pinfunction "D1_44") (pintype "bidirectional"))
      (node (ref "5") (pin "44") (pinfunction "D1_44") (pintype "bidirectional"))
      (node (ref "6") (pin "44") (pinfunction "D1_44") (pintype "bidirectional"))
      (node (ref "7") (pin "44") (pinfunction "D1_44") (pintype "bidirectional"))
      (node (ref "RN2") (pin "9") (pinfunction "9_9") (pintype "passive"))
      (node (ref "RN8") (pin "9") (pinfunction "9_9") (pintype "passive"))
    )
    (net (code "73") (name "D2") (class "Default")
      (node (ref "0") (pin "45") (pinfunction "D2_45") (pintype "bidirectional"))
      (node (ref "1") (pin "45") (pinfunction "D2_45") (pintype "bidirectional"))
      (node (ref "2") (pin "45") (pinfunction "D2_45") (pintype "bidirectional"))
      (node (ref "3") (pin "45") (pinfunction "D2_45") (pintype "bidirectional"))
      (node (ref "4") (pin "45") (pinfunction "D2_45") (pintype "bidirectional"))
      (node (ref "5") (pin "45") (pinfunction "D2_45") (pintype "bidirectional"))
      (node (ref "6") (pin "45") (pinfunction "D2_45") (pintype "bidirectional"))
      (node (ref "7") (pin "45") (pinfunction "D2_45") (pintype "bidirectional"))
      (node (ref "RN12") (pin "9") (pinfunction "9_9") (pintype "passive"))
      (node (ref "RN6") (pin "9") (pinfunction "9_9") (pintype "passive"))
    )
    (net (code "74") (name "D3") (class "Default")
      (node (ref "0") (pin "46") (pinfunction "D3_46") (pintype "bidirectional"))
      (node (ref "1") (pin "46") (pinfunction "D3_46") (pintype "bidirectional"))
      (node (ref "2") (pin "46") (pinfunction "D3_46") (pintype "bidirectional"))
      (node (ref "3") (pin "46") (pinfunction "D3_46") (pintype "bidirectional"))
      (node (ref "4") (pin "46") (pinfunction "D3_46") (pintype "bidirectional"))
      (node (ref "5") (pin "46") (pinfunction "D3_46") (pintype "bidirectional"))
      (node (ref "6") (pin "46") (pinfunction "D3_46") (pintype "bidirectional"))
      (node (ref "7") (pin "46") (pinfunction "D3_46") (pintype "bidirectional"))
      (node (ref "RN3") (pin "9") (pinfunction "9_9") (pintype "passive"))
      (node (ref "RN9") (pin "9") (pinfunction "9_9") (pintype "passive"))
    )
    (net (code "75") (name "D4") (class "Default")
      (node (ref "0") (pin "47") (pinfunction "D4_47") (pintype "bidirectional"))
      (node (ref "1") (pin "47") (pinfunction "D4_47") (pintype "bidirectional"))
      (node (ref "2") (pin "47") (pinfunction "D4_47") (pintype "bidirectional"))
      (node (ref "3") (pin "47") (pinfunction "D4_47") (pintype "bidirectional"))
      (node (ref "4") (pin "47") (pinfunction "D4_47") (pintype "bidirectional"))
      (node (ref "5") (pin "47") (pinfunction "D4_47") (pintype "bidirectional"))
      (node (ref "6") (pin "47") (pinfunction "D4_47") (pintype "bidirectional"))
      (node (ref "7") (pin "47") (pinfunction "D4_47") (pintype "bidirectional"))
      (node (ref "RN12") (pin "8") (pinfunction "8_8") (pintype "passive"))
      (node (ref "RN6") (pin "8") (pinfunction "8_8") (pintype "passive"))
    )
    (net (code "76") (name "D5") (class "Default")
      (node (ref "0") (pin "48") (pinfunction "D5_48") (pintype "bidirectional"))
      (node (ref "1") (pin "48") (pinfunction "D5_48") (pintype "bidirectional"))
      (node (ref "2") (pin "48") (pinfunction "D5_48") (pintype "bidirectional"))
      (node (ref "3") (pin "48") (pinfunction "D5_48") (pintype "bidirectional"))
      (node (ref "4") (pin "48") (pinfunction "D5_48") (pintype "bidirectional"))
      (node (ref "5") (pin "48") (pinfunction "D5_48") (pintype "bidirectional"))
      (node (ref "6") (pin "48") (pinfunction "D5_48") (pintype "bidirectional"))
      (node (ref "7") (pin "48") (pinfunction "D5_48") (pintype "bidirectional"))
      (node (ref "RN3") (pin "8") (pinfunction "8_8") (pintype "passive"))
      (node (ref "RN9") (pin "8") (pinfunction "8_8") (pintype "passive"))
    )
    (net (code "77") (name "D6") (class "Default")
      (node (ref "0") (pin "49") (pinfunction "D6_49") (pintype "bidirectional"))
      (node (ref "1") (pin "49") (pinfunction "D6_49") (pintype "bidirectional"))
      (node (ref "2") (pin "49") (pinfunction "D6_49") (pintype "bidirectional"))
      (node (ref "3") (pin "49") (pinfunction "D6_49") (pintype "bidirectional"))
      (node (ref "4") (pin "49") (pinfunction "D6_49") (pintype "bidirectional"))
      (node (ref "5") (pin "49") (pinfunction "D6_49") (pintype "bidirectional"))
      (node (ref "6") (pin "49") (pinfunction "D6_49") (pintype "bidirectional"))
      (node (ref "7") (pin "49") (pinfunction "D6_49") (pintype "bidirectional"))
      (node (ref "RN12") (pin "7") (pinfunction "7_7") (pintype "passive"))
      (node (ref "RN6") (pin "7") (pinfunction "7_7") (pintype "passive"))
    )
    (net (code "78") (name "D7") (class "Default")
      (node (ref "0") (pin "50") (pinfunction "D7_50") (pintype "bidirectional"))
      (node (ref "1") (pin "50") (pinfunction "D7_50") (pintype "bidirectional"))
      (node (ref "2") (pin "50") (pinfunction "D7_50") (pintype "bidirectional"))
      (node (ref "3") (pin "50") (pinfunction "D7_50") (pintype "bidirectional"))
      (node (ref "4") (pin "50") (pinfunction "D7_50") (pintype "bidirectional"))
      (node (ref "5") (pin "50") (pinfunction "D7_50") (pintype "bidirectional"))
      (node (ref "6") (pin "50") (pinfunction "D7_50") (pintype "bidirectional"))
      (node (ref "7") (pin "50") (pinfunction "D7_50") (pintype "bidirectional"))
      (node (ref "RN3") (pin "7") (pinfunction "7_7") (pintype "passive"))
      (node (ref "RN9") (pin "7") (pinfunction "7_7") (pintype "passive"))
    )
    (net (code "79") (name "GND") (class "Default")
      (node (ref "0") (pin "3") (pinfunction "GND_3") (pintype "bidirectional"))
      (node (ref "0") (pin "4") (pinfunction "GND_4") (pintype "bidirectional"))
      (node (ref "0") (pin "62") (pinfunction "GND_62") (pintype "bidirectional"))
      (node (ref "1") (pin "3") (pinfunction "GND_3") (pintype "bidirectional"))
      (node (ref "1") (pin "4") (pinfunction "GND_4") (pintype "bidirectional"))
      (node (ref "1") (pin "62") (pinfunction "GND_62") (pintype "bidirectional"))
      (node (ref "2") (pin "3") (pinfunction "GND_3") (pintype "bidirectional"))
      (node (ref "2") (pin "4") (pinfunction "GND_4") (pintype "bidirectional"))
      (node (ref "2") (pin "62") (pinfunction "GND_62") (pintype "bidirectional"))
      (node (ref "3") (pin "3") (pinfunction "GND_3") (pintype "bidirectional"))
      (node (ref "3") (pin "4") (pinfunction "GND_4") (pintype "bidirectional"))
      (node (ref "3") (pin "62") (pinfunction "GND_62") (pintype "bidirectional"))
      (node (ref "4") (pin "3") (pinfunction "GND_3") (pintype "bidirectional"))
      (node (ref "4") (pin "4") (pinfunction "GND_4") (pintype "bidirectional"))
      (node (ref "4") (pin "62") (pinfunction "GND_62") (pintype "bidirectional"))
      (node (ref "5") (pin "3") (pinfunction "GND_3") (pintype "bidirectional"))
      (node (ref "5") (pin "4") (pinfunction "GND_4") (pintype "bidirectional"))
      (node (ref "5") (pin "62") (pinfunction "GND_62") (pintype "bidirectional"))
      (node (ref "6") (pin "3") (pinfunction "GND_3") (pintype "bidirectional"))
      (node (ref "6") (pin "4") (pinfunction "GND_4") (pintype "bidirectional"))
      (node (ref "6") (pin "62") (pinfunction "GND_62") (pintype "bidirectional"))
      (node (ref "7") (pin "3") (pinfunction "GND_3") (pintype "bidirectional"))
      (node (ref "7") (pin "4") (pinfunction "GND_4") (pintype "bidirectional"))
      (node (ref "7") (pin "62") (pinfunction "GND_62") (pintype "bidirectional"))
      (node (ref "C1") (pin "2") (pinfunction "2_2") (pintype "passive"))
      (node (ref "C10") (pin "2") (pinfunction "2_2") (pintype "passive"))
      (node (ref "C11") (pin "2") (pinfunction "2_2") (pintype "passive"))
      (node (ref "C12") (pin "2") (pinfunction "2_2") (pintype "passive"))
      (node (ref "C13") (pin "2") (pinfunction "2_2") (pintype "passive"))
      (node (ref "C14") (pin "2") (pinfunction "2_2") (pintype "passive"))
      (node (ref "C15") (pin "2") (pinfunction "2_2") (pintype "passive"))
      (node (ref "C16") (pin "2") (pinfunction "2_2") (pintype "passive"))
      (node (ref "C17") (pin "2") (pinfunction "2_2") (pintype "passive"))
      (node (ref "C18") (pin "2") (pinfunction "2_2") (pintype "passive"))
      (node (ref "C19") (pin "2") (pinfunction "2_2") (pintype "passive"))
      (node (ref "C2") (pin "2") (pinfunction "2_2") (pintype "passive"))
      (node (ref "C20") (pin "2") (pinfunction "2_2") (pintype "passive"))
      (node (ref "C21") (pin "2") (pinfunction "2_2") (pintype "passive"))
      (node (ref "C22") (pin "2") (pinfunction "2_2") (pintype "passive"))
      (node (ref "C23") (pin "2") (pinfunction "2_2") (pintype "passive"))
      (node (ref "C24") (pin "2") (pinfunction "2_2") (pintype "passive"))
      (node (ref "C25") (pin "2") (pinfunction "2_2") (pintype "passive"))
      (node (ref "C26") (pin "2") (pinfunction "2_2") (pintype "passive"))
      (node (ref "C27") (pin "2") (pinfunction "2_2") (pintype "passive"))
      (node (ref "C28") (pin "2") (pinfunction "2_2") (pintype "passive"))
      (node (ref "C29") (pin "2") (pinfunction "2_2") (pintype "passive"))
      (node (ref "C3") (pin "2") (pinfunction "2_2") (pintype "passive"))
      (node (ref "C30") (pin "2") (pinfunction "2_2") (pintype "passive"))
      (node (ref "C31") (pin "2") (pinfunction "2_2") (pintype "passive"))
      (node (ref "C32") (pin "2") (pinfunction "2_2") (pintype "passive"))
      (node (ref "C34") (pin "2") (pinfunction "2_2") (pintype "passive"))
      (node (ref "C35") (pin "2") (pinfunction "2_2") (pintype "passive"))
      (node (ref "C36") (pin "2") (pinfunction "2_2") (pintype "passive"))
      (node (ref "C37") (pin "2") (pinfunction "2_2") (pintype "passive"))
      (node (ref "C38") (pin "2") (pinfunction "2_2") (pintype "passive"))
      (node (ref "C39") (pin "2") (pinfunction "2_2") (pintype "passive"))
      (node (ref "C4") (pin "2") (pinfunction "2_2") (pintype "passive"))
      (node (ref "C40") (pin "2") (pinfunction "2_2") (pintype "passive"))
      (node (ref "C41") (pin "2") (pinfunction "2_2") (pintype "passive"))
      (node (ref "C42") (pin "2") (pinfunction "2_2") (pintype "passive"))
      (node (ref "C43") (pin "2") (pinfunction "2_2") (pintype "passive"))
      (node (ref "C44") (pin "2") (pinfunction "2_2") (pintype "passive"))
      (node (ref "C45") (pin "-") (pinfunction "-_-") (pintype "passive"))
      (node (ref "C46") (pin "2") (pinfunction "2_2") (pintype "passive"))
      (node (ref "C47") (pin "-") (pinfunction "-_-") (pintype "passive"))
      (node (ref "C48") (pin "-") (pinfunction "-_-") (pintype "passive"))
      (node (ref "C49") (pin "-") (pinfunction "-_-") (pintype "passive"))
      (node (ref "C5") (pin "2") (pinfunction "2_2") (pintype "passive"))
      (node (ref "C50") (pin "-") (pinfunction "-_-") (pintype "passive"))
      (node (ref "C51") (pin "-") (pinfunction "-_-") (pintype "passive"))
      (node (ref "C52") (pin "2") (pinfunction "2_2") (pintype "passive"))
      (node (ref "C53") (pin "2") (pinfunction "2_2") (pintype "passive"))
      (node (ref "C54") (pin "2") (pinfunction "2_2") (pintype "passive"))
      (node (ref "C55") (pin "2") (pinfunction "2_2") (pintype "passive"))
      (node (ref "C57") (pin "-") (pinfunction "-_-") (pintype "passive"))
      (node (ref "C6") (pin "2") (pinfunction "2_2") (pintype "passive"))
      (node (ref "C7") (pin "2") (pinfunction "2_2") (pintype "passive"))
      (node (ref "C8") (pin "2") (pinfunction "2_2") (pintype "passive"))
      (node (ref "C9") (pin "2") (pinfunction "2_2") (pintype "passive"))
      (node (ref "D3") (pin "K") (pinfunction "C_K") (pintype "passive"))
      (node (ref "J1") (pin "15") (pinfunction "GND_15") (pintype "bidirectional"))
      (node (ref "J1") (pin "17") (pinfunction "GND_17") (pintype "bidirectional"))
      (node (ref "J1") (pin "18") (pinfunction "GND_18") (pintype "bidirectional"))
      (node (ref "J1") (pin "19") (pinfunction "GND_19") (pintype "bidirectional"))
      (node (ref "J1") (pin "24") (pinfunction "GND_24") (pintype "bidirectional"))
      (node (ref "J1") (pin "3") (pinfunction "GND_3") (pintype "bidirectional"))
      (node (ref "J1") (pin "5") (pinfunction "GND_5") (pintype "bidirectional"))
      (node (ref "J1") (pin "7") (pinfunction "GND_7") (pintype "bidirectional"))
      (node (ref "J2") (pin "2") (pinfunction "2_2") (pintype "passive"))
      (node (ref "JP5") (pin "3") (pinfunction "3_3") (pintype "passive"))
      (node (ref "Q1") (pin "1") (pinfunction "E_1") (pintype "passive"))
      (node (ref "Q3") (pin "1") (pinfunction "E_1") (pintype "passive"))
      (node (ref "R5") (pin "1") (pinfunction "1_1") (pintype "passive"))
      (node (ref "RN15") (pin "1") (pinfunction "1_1") (pintype "passive"))
      (node (ref "S1") (pin "P$1") (pinfunction "P$1_P$1") (pintype "bidirectional"))
      (node (ref "U5") (pin "2") (pinfunction "GND_2") (pintype "passive"))
      (node (ref "U9") (pin "1") (pinfunction "GND_1") (pintype "power_in"))
    )
    (net (code "80") (name "Net-(C34-Pad1)") (class "Default")
      (node (ref "C34") (pin "1") (pinfunction "1_1") (pintype "passive"))
      (node (ref "C35") (pin "1") (pinfunction "1_1") (pintype "passive"))
      (node (ref "C36") (pin "1") (pinfunction "1_1") (pintype "passive"))
      (node (ref "JP1") (pin "2") (pinfunction "2_2") (pintype "passive"))
      (node (ref "R1") (pin "1") (pinfunction "1_1") (pintype "passive"))
      (node (ref "RN1") (pin "1") (pinfunction "1_1") (pintype "passive"))
      (node (ref "RN2") (pin "1") (pinfunction "1_1") (pintype "passive"))
      (node (ref "RN3") (pin "1") (pinfunction "1_1") (pintype "passive"))
      (node (ref "RN4") (pin "1") (pinfunction "1_1") (pintype "passive"))
      (node (ref "RN5") (pin "1") (pinfunction "1_1") (pintype "passive"))
      (node (ref "RN6") (pin "1") (pinfunction "1_1") (pintype "passive"))
    )
    (net (code "81") (name "Net-(C37-Pad1)") (class "Default")
      (node (ref "C37") (pin "1") (pinfunction "1_1") (pintype "passive"))
      (node (ref "C38") (pin "1") (pinfunction "1_1") (pintype "passive"))
      (node (ref "C39") (pin "1") (pinfunction "1_1") (pintype "passive"))
      (node (ref "JP2") (pin "2") (pinfunction "2_2") (pintype "passive"))
      (node (ref "R2") (pin "1") (pinfunction "1_1") (pintype "passive"))
      (node (ref "RN10") (pin "1") (pinfunction "1_1") (pintype "passive"))
      (node (ref "RN11") (pin "1") (pinfunction "1_1") (pintype "passive"))
      (node (ref "RN12") (pin "1") (pinfunction "1_1") (pintype "passive"))
      (node (ref "RN7") (pin "1") (pinfunction "1_1") (pintype "passive"))
      (node (ref "RN8") (pin "1") (pinfunction "1_1") (pintype "passive"))
      (node (ref "RN9") (pin "1") (pinfunction "1_1") (pintype "passive"))
    )
    (net (code "82") (name "Net-(C56-Pad2)") (class "Default")
      (node (ref "C56") (pin "2") (pinfunction "2_2") (pintype "passive"))
      (node (ref "JP5") (pin "2") (pinfunction "2_2") (pintype "passive"))
    )
    (net (code "83") (name "Net-(D1-PadA)") (class "Default")
      (node (ref "D1") (pin "A") (pinfunction "A_A") (pintype "passive"))
      (node (ref "JP3") (pin "1") (pinfunction "1_1") (pintype "passive"))
    )
    (net (code "84") (name "Net-(D2-C)") (class "Default")
      (node (ref "D2") (pin "K") (pinfunction "C_K") (pintype "passive"))
      (node (ref "JP5") (pin "1") (pinfunction "1_1") (pintype "passive"))
      (node (ref "Q1") (pin "3") (pinfunction "C_3") (pintype "passive"))
    )
    (net (code "85") (name "Net-(D2-PadA)") (class "Default")
      (node (ref "D2") (pin "A") (pinfunction "A_A") (pintype "passive"))
      (node (ref "R11") (pin "1") (pinfunction "1_1") (pintype "passive"))
    )
    (net (code "86") (name "Net-(D3-PadA)") (class "Default")
      (node (ref "D3") (pin "A") (pinfunction "A_A") (pintype "passive"))
      (node (ref "R12") (pin "1") (pinfunction "1_1") (pintype "passive"))
    )
    (net (code "87") (name "Net-(J1-PS_ON)") (class "Default")
      (node (ref "J1") (pin "16") (pinfunction "PS_ON_16") (pintype "bidirectional"))
      (node (ref "J2") (pin "1") (pinfunction "1_1") (pintype "passive"))
      (node (ref "S1") (pin "P$2") (pinfunction "P$2_P$2") (pintype "bidirectional"))
    )
    (net (code "88") (name "Net-(Q1-B)") (class "Default")
      (node (ref "Q1") (pin "2") (pinfunction "B_2") (pintype "passive"))
      (node (ref "R6") (pin "2") (pinfunction "2_2") (pintype "passive"))
    )
    (net (code "89") (name "Net-(Q2-B)") (class "Default")
      (node (ref "Q2") (pin "2") (pinfunction "B_2") (pintype "passive"))
      (node (ref "R10") (pin "2") (pinfunction "2_2") (pintype "passive"))
    )
    (net (code "90") (name "Net-(Q2-C)") (class "Default")
      (node (ref "Q2") (pin "3") (pinfunction "C_3") (pintype "passive"))
      (node (ref "R12") (pin "2") (pinfunction "2_2") (pintype "passive"))
    )
    (net (code "91") (name "Net-(Q3-B)") (class "Default")
      (node (ref "Q3") (pin "2") (pinfunction "B_2") (pintype "passive"))
      (node (ref "R9") (pin "2") (pinfunction "2_2") (pintype "passive"))
    )
    (net (code "92") (name "Net-(Q3-C)") (class "Default")
      (node (ref "JP7") (pin "1") (pinfunction "1_1") (pintype "passive"))
      (node (ref "Q3") (pin "3") (pinfunction "C_3") (pintype "passive"))
    )
    (net (code "93") (name "Net-(U1A-I0)") (class "Default")
      (node (ref "U1") (pin "1") (pinfunction "I0_1") (pintype "input"))
      (node (ref "U2") (pin "2") (pinfunction "O_2") (pintype "output"))
    )
    (net (code "94") (name "Net-(U1A-O)") (class "Default")
      (node (ref "R3") (pin "1") (pinfunction "1_1") (pintype "passive"))
      (node (ref "U1") (pin "3") (pinfunction "O_3") (pintype "output"))
    )
    (net (code "95") (name "Net-(U2A-I)") (class "Default")
      (node (ref "U2") (pin "1") (pinfunction "I_1") (pintype "input"))
      (node (ref "U3") (pin "8") (pinfunction "O_8") (pintype "output"))
    )
    (net (code "96") (name "Net-(U2B-I)") (class "Default")
      (node (ref "U2") (pin "3") (pinfunction "I_3") (pintype "input"))
      (node (ref "U4") (pin "8") (pinfunction "O_8") (pintype "output"))
    )
    (net (code "97") (name "Net-(U2B-O)") (class "Default")
      (node (ref "R4") (pin "1") (pinfunction "1_1") (pintype "passive"))
      (node (ref "U2") (pin "4") (pinfunction "O_4") (pintype "output"))
    )
    (net (code "98") (name "Net-(U5-VI)") (class "Default")
      (node (ref "C44") (pin "1") (pinfunction "1_1") (pintype "passive"))
      (node (ref "D1") (pin "C") (pinfunction "C_C") (pintype "passive"))
      (node (ref "U5") (pin "1") (pinfunction "VI_1") (pintype "input"))
    )
    (net (code "99") (name "Net-(U5-VO)") (class "Default")
      (node (ref "C45") (pin "+") (pinfunction "+_+") (pintype "passive"))
      (node (ref "C46") (pin "1") (pinfunction "1_1") (pintype "passive"))
      (node (ref "JP1") (pin "3") (pinfunction "3_3") (pintype "passive"))
      (node (ref "JP2") (pin "3") (pinfunction "3_3") (pintype "passive"))
      (node (ref "U5") (pin "3") (pinfunction "VO_3") (pintype "passive"))
    )
    (net (code "100") (name "Net-(U8A-G)") (class "Default")
      (node (ref "JP4") (pin "2") (pinfunction "2_2") (pintype "passive"))
      (node (ref "R5") (pin "2") (pinfunction "2_2") (pintype "passive"))
      (node (ref "U8") (pin "1") (pinfunction "G_1") (pintype "input"))
    )
    (net (code "101") (name "Net-(U8A-Q0)") (class "Default")
      (node (ref "RN15") (pin "9") (pinfunction "9_9") (pintype "passive"))
      (node (ref "S2") (pin "9") (pinfunction "9_9") (pintype "passive"))
      (node (ref "U8") (pin "3") (pinfunction "Q0_3") (pintype "input"))
    )
    (net (code "102") (name "Net-(U8A-Q1)") (class "Default")
      (node (ref "RN15") (pin "7") (pinfunction "7_7") (pintype "passive"))
      (node (ref "S2") (pin "11") (pinfunction "11_11") (pintype "passive"))
      (node (ref "U8") (pin "5") (pinfunction "Q1_5") (pintype "input"))
    )
    (net (code "103") (name "Net-(U8A-Q2)") (class "Default")
      (node (ref "RN15") (pin "5") (pinfunction "5_5") (pintype "passive"))
      (node (ref "S2") (pin "13") (pinfunction "13_13") (pintype "passive"))
      (node (ref "U8") (pin "7") (pinfunction "Q2_7") (pintype "input"))
    )
    (net (code "104") (name "Net-(U8A-Q3)") (class "Default")
      (node (ref "RN15") (pin "3") (pinfunction "3_3") (pintype "passive"))
      (node (ref "S2") (pin "15") (pinfunction "15_15") (pintype "passive"))
      (node (ref "U8") (pin "9") (pinfunction "Q3_9") (pintype "input"))
    )
    (net (code "105") (name "Net-(U8A-Q4)") (class "Default")
      (node (ref "RN15") (pin "2") (pinfunction "2_2") (pintype "passive"))
      (node (ref "S2") (pin "16") (pinfunction "16_16") (pintype "passive"))
      (node (ref "U8") (pin "12") (pinfunction "Q4_12") (pintype "input"))
    )
    (net (code "106") (name "Net-(U8A-Q5)") (class "Default")
      (node (ref "RN15") (pin "4") (pinfunction "4_4") (pintype "passive"))
      (node (ref "S2") (pin "14") (pinfunction "14_14") (pintype "passive"))
      (node (ref "U8") (pin "14") (pinfunction "Q5_14") (pintype "input"))
    )
    (net (code "107") (name "Net-(U8A-Q6)") (class "Default")
      (node (ref "RN15") (pin "6") (pinfunction "6_6") (pintype "passive"))
      (node (ref "S2") (pin "12") (pinfunction "12_12") (pintype "passive"))
      (node (ref "U8") (pin "16") (pinfunction "Q6_16") (pintype "input"))
    )
    (net (code "108") (name "Net-(U8A-Q7)") (class "Default")
      (node (ref "RN15") (pin "8") (pinfunction "8_8") (pintype "passive"))
      (node (ref "S2") (pin "10") (pinfunction "10_10") (pintype "passive"))
      (node (ref "U8") (pin "18") (pinfunction "Q7_18") (pintype "input"))
    )
    (net (code "109") (name "Net-(U9-CON)") (class "Default")
      (node (ref "C55") (pin "1") (pinfunction "1_1") (pintype "passive"))
      (node (ref "U9") (pin "5") (pinfunction "CON_5") (pintype "input"))
    )
    (net (code "110") (name "Net-(U9-DIS)") (class "Default")
      (node (ref "C57") (pin "+") (pinfunction "+_+") (pintype "passive"))
      (node (ref "R8") (pin "2") (pinfunction "2_2") (pintype "passive"))
      (node (ref "U9") (pin "6") (pinfunction "TRE_6") (pintype "input"))
      (node (ref "U9") (pin "7") (pinfunction "DIS_7") (pintype "input"))
    )
    (net (code "111") (name "Net-(U9-OUT)") (class "Default")
      (node (ref "R9") (pin "1") (pinfunction "1_1") (pintype "passive"))
      (node (ref "U9") (pin "3") (pinfunction "OUT_3") (pintype "output"))
    )
    (net (code "112") (name "Net-(U9-TRI)") (class "Default")
      (node (ref "C56") (pin "1") (pinfunction "1_1") (pintype "passive"))
      (node (ref "R7") (pin "2") (pinfunction "2_2") (pintype "passive"))
      (node (ref "U9") (pin "2") (pinfunction "TRI_2") (pintype "input"))
    )
    (net (code "113") (name "Net-(U9-VCC+)") (class "Default")
      (node (ref "C54") (pin "1") (pinfunction "1_1") (pintype "passive"))
      (node (ref "JP6") (pin "2") (pinfunction "2_2") (pintype "passive"))
      (node (ref "R7") (pin "1") (pinfunction "1_1") (pintype "passive"))
      (node (ref "R8") (pin "1") (pinfunction "1_1") (pintype "passive"))
      (node (ref "U9") (pin "4") (pinfunction "/RES_4") (pintype "input"))
      (node (ref "U9") (pin "8") (pinfunction "VCC+_8") (pintype "power_in"))
    )
    (net (code "114") (name "PG") (class "Default")
      (node (ref "J1") (pin "8") (pinfunction "PWR_OK_8") (pintype "bidirectional"))
      (node (ref "R6") (pin "1") (pinfunction "1_1") (pintype "passive"))
    )
    (net (code "115") (name "VCC") (class "Default")
      (node (ref "0") (pin "5") (pinfunction "+5V_5") (pintype "bidirectional"))
      (node (ref "0") (pin "6") (pinfunction "+5V_6") (pintype "bidirectional"))
      (node (ref "1") (pin "5") (pinfunction "+5V_5") (pintype "bidirectional"))
      (node (ref "1") (pin "6") (pinfunction "+5V_6") (pintype "bidirectional"))
      (node (ref "2") (pin "5") (pinfunction "+5V_5") (pintype "bidirectional"))
      (node (ref "2") (pin "6") (pinfunction "+5V_6") (pintype "bidirectional"))
      (node (ref "3") (pin "5") (pinfunction "+5V_5") (pintype "bidirectional"))
      (node (ref "3") (pin "6") (pinfunction "+5V_6") (pintype "bidirectional"))
      (node (ref "4") (pin "5") (pinfunction "+5V_5") (pintype "bidirectional"))
      (node (ref "4") (pin "6") (pinfunction "+5V_6") (pintype "bidirectional"))
      (node (ref "5") (pin "5") (pinfunction "+5V_5") (pintype "bidirectional"))
      (node (ref "5") (pin "6") (pinfunction "+5V_6") (pintype "bidirectional"))
      (node (ref "6") (pin "5") (pinfunction "+5V_5") (pintype "bidirectional"))
      (node (ref "6") (pin "6") (pinfunction "+5V_6") (pintype "bidirectional"))
      (node (ref "7") (pin "5") (pinfunction "+5V_5") (pintype "bidirectional"))
      (node (ref "7") (pin "6") (pinfunction "+5V_6") (pintype "bidirectional"))
      (node (ref "C10") (pin "1") (pinfunction "1_1") (pintype "passive"))
      (node (ref "C14") (pin "1") (pinfunction "1_1") (pintype "passive"))
      (node (ref "C18") (pin "1") (pinfunction "1_1") (pintype "passive"))
      (node (ref "C2") (pin "1") (pinfunction "1_1") (pintype "passive"))
      (node (ref "C22") (pin "1") (pinfunction "1_1") (pintype "passive"))
      (node (ref "C26") (pin "1") (pinfunction "1_1") (pintype "passive"))
      (node (ref "C30") (pin "1") (pinfunction "1_1") (pintype "passive"))
      (node (ref "C40") (pin "1") (pinfunction "1_1") (pintype "passive"))
      (node (ref "C41") (pin "1") (pinfunction "1_1") (pintype "passive"))
      (node (ref "C42") (pin "1") (pinfunction "1_1") (pintype "passive"))
      (node (ref "C43") (pin "1") (pinfunction "1_1") (pintype "passive"))
      (node (ref "C49") (pin "+") (pinfunction "+_+") (pintype "passive"))
      (node (ref "C52") (pin "1") (pinfunction "1_1") (pintype "passive"))
      (node (ref "C53") (pin "1") (pinfunction "1_1") (pintype "passive"))
      (node (ref "C6") (pin "1") (pinfunction "1_1") (pintype "passive"))
      (node (ref "J1") (pin "21") (pinfunction "5V_21") (pintype "bidirectional"))
      (node (ref "J1") (pin "22") (pinfunction "5V_22") (pintype "bidirectional"))
      (node (ref "J1") (pin "23") (pinfunction "5V_23") (pintype "bidirectional"))
      (node (ref "J1") (pin "4") (pinfunction "5V_4") (pintype "bidirectional"))
      (node (ref "J1") (pin "6") (pinfunction "5V_6") (pintype "bidirectional"))
      (node (ref "JP1") (pin "1") (pinfunction "1_1") (pintype "passive"))
      (node (ref "JP2") (pin "1") (pinfunction "1_1") (pintype "passive"))
      (node (ref "JP3") (pin "2") (pinfunction "2_2") (pintype "passive"))
      (node (ref "JP4") (pin "1") (pinfunction "1_1") (pintype "passive"))
      (node (ref "JP6") (pin "1") (pinfunction "1_1") (pintype "passive"))
      (node (ref "Q2") (pin "1") (pinfunction "E_1") (pintype "passive"))
      (node (ref "R11") (pin "2") (pinfunction "2_2") (pintype "passive"))
      (node (ref "RN13") (pin "1") (pinfunction "1_1") (pintype "passive"))
      (node (ref "RN14") (pin "1") (pinfunction "1_1") (pintype "passive"))
      (node (ref "S2") (pin "1") (pinfunction "1_1") (pintype "passive"))
      (node (ref "S2") (pin "2") (pinfunction "2_2") (pintype "passive"))
      (node (ref "S2") (pin "3") (pinfunction "3_3") (pintype "passive"))
      (node (ref "S2") (pin "4") (pinfunction "4_4") (pintype "passive"))
      (node (ref "S2") (pin "5") (pinfunction "5_5") (pintype "passive"))
      (node (ref "S2") (pin "6") (pinfunction "6_6") (pintype "passive"))
      (node (ref "S2") (pin "7") (pinfunction "7_7") (pintype "passive"))
      (node (ref "S2") (pin "8") (pinfunction "8_8") (pintype "passive"))
      (node (ref "U1") (pin "10") (pinfunction "I1_10") (pintype "input"))
      (node (ref "U1") (pin "12") (pinfunction "I0_12") (pintype "input"))
      (node (ref "U1") (pin "13") (pinfunction "I1_13") (pintype "input"))
      (node (ref "U1") (pin "4") (pinfunction "I0_4") (pintype "input"))
      (node (ref "U1") (pin "5") (pinfunction "I1_5") (pintype "input"))
      (node (ref "U1") (pin "9") (pinfunction "I0_9") (pintype "input"))
      (node (ref "U2") (pin "11") (pinfunction "I_11") (pintype "input"))
      (node (ref "U2") (pin "13") (pinfunction "I_13") (pintype "input"))
      (node (ref "U2") (pin "5") (pinfunction "I_5") (pintype "input"))
      (node (ref "U2") (pin "9") (pinfunction "I_9") (pintype "input"))
      (node (ref "U7") (pin "6") (pinfunction "G1_6") (pintype "input"))
    )
    (net (code "116") (name "unconnected-(J1-3.3V-Pad12)") (class "Default")
      (node (ref "J1") (pin "12") (pinfunction "3.3V_12") (pintype "bidirectional"))
    )
    (net (code "117") (name "unconnected-(J1-NC-Pad20)") (class "Default")
      (node (ref "J1") (pin "20") (pinfunction "NC_20") (pintype "bidirectional"))
    )
    (net (code "118") (name "unconnected-(S1-PadP$3)") (class "Default")
      (node (ref "S1") (pin "P$3") (pinfunction "P$3_P$3") (pintype "bidirectional"))
    )
    (net (code "119") (name "unconnected-(U1B-O-Pad6)") (class "Default")
      (node (ref "U1") (pin "6") (pinfunction "O_6") (pintype "output"))
    )
    (net (code "120") (name "unconnected-(U1C-O-Pad8)") (class "Default")
      (node (ref "U1") (pin "8") (pinfunction "O_8") (pintype "output"))
    )
    (net (code "121") (name "unconnected-(U1D-O-Pad11)") (class "Default")
      (node (ref "U1") (pin "11") (pinfunction "O_11") (pintype "output"))
    )
    (net (code "122") (name "unconnected-(U2C-O-Pad6)") (class "Default")
      (node (ref "U2") (pin "6") (pinfunction "O_6") (pintype "output"))
    )
    (net (code "123") (name "unconnected-(U2D-O-Pad8)") (class "Default")
      (node (ref "U2") (pin "8") (pinfunction "O_8") (pintype "output"))
    )
    (net (code "124") (name "unconnected-(U2E-O-Pad10)") (class "Default")
      (node (ref "U2") (pin "10") (pinfunction "O_10") (pintype "output"))
    )
    (net (code "125") (name "unconnected-(U2F-O-Pad12)") (class "Default")
      (node (ref "U2") (pin "12") (pinfunction "O_12") (pintype "output"))
    )
  )
)
